# OpenDeck-r2_1_0.net
KiCad netlist of a schematic drawn in EAGLE
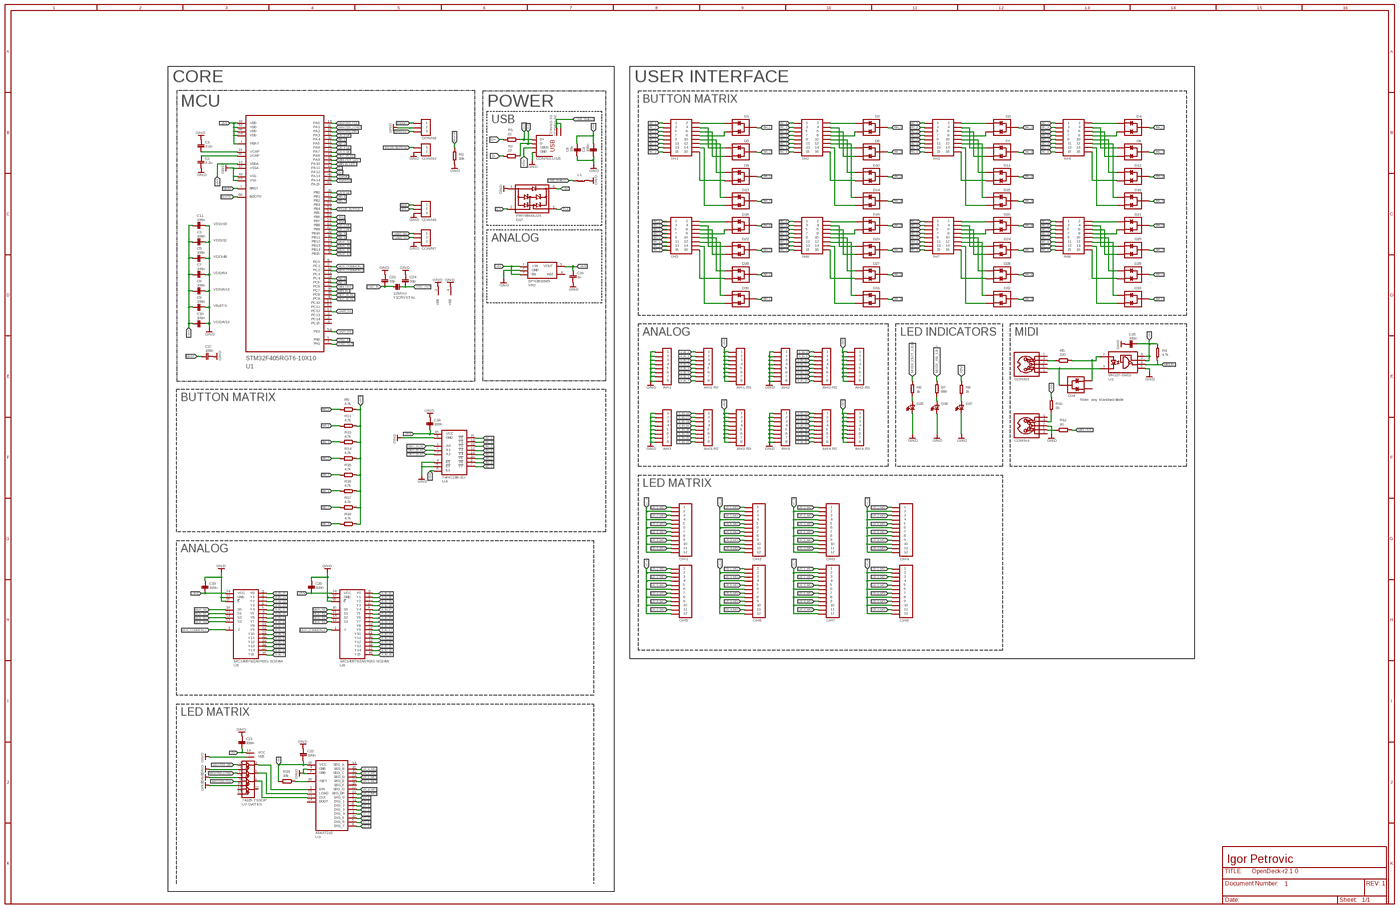
[diagram p0: schematic, sheet 1, overview]
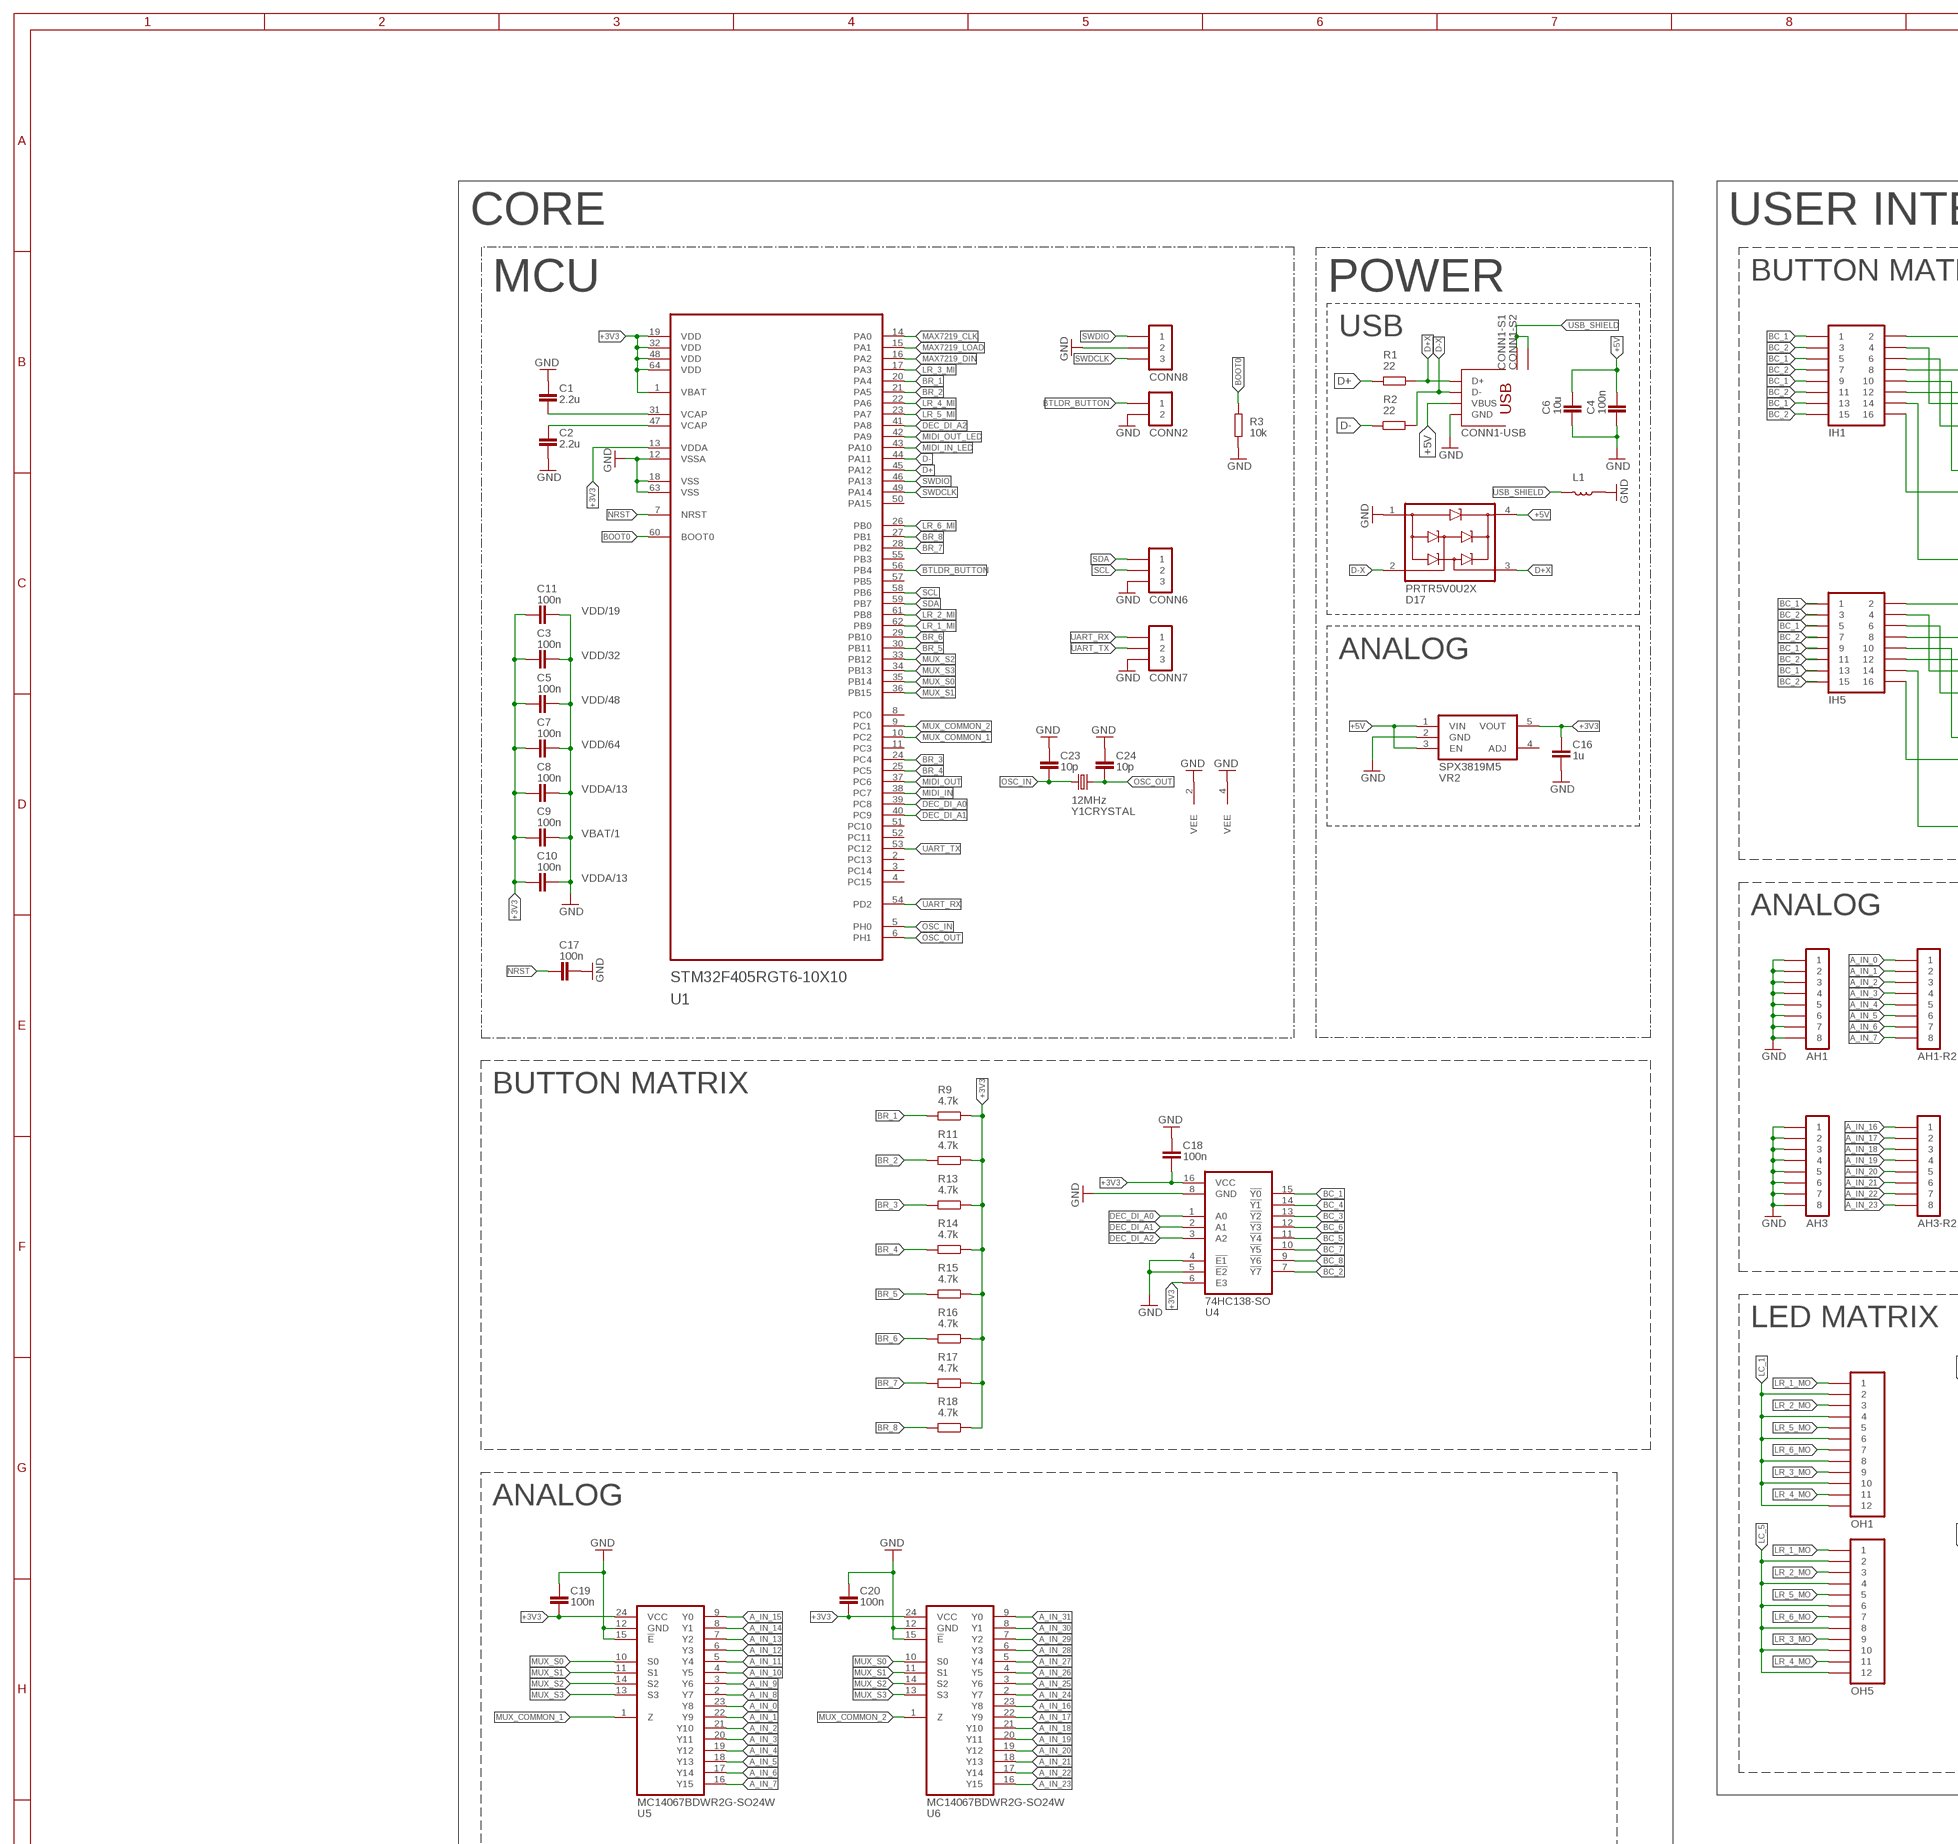
[diagram p1: schematic, sheet 1, part 1 of 4]
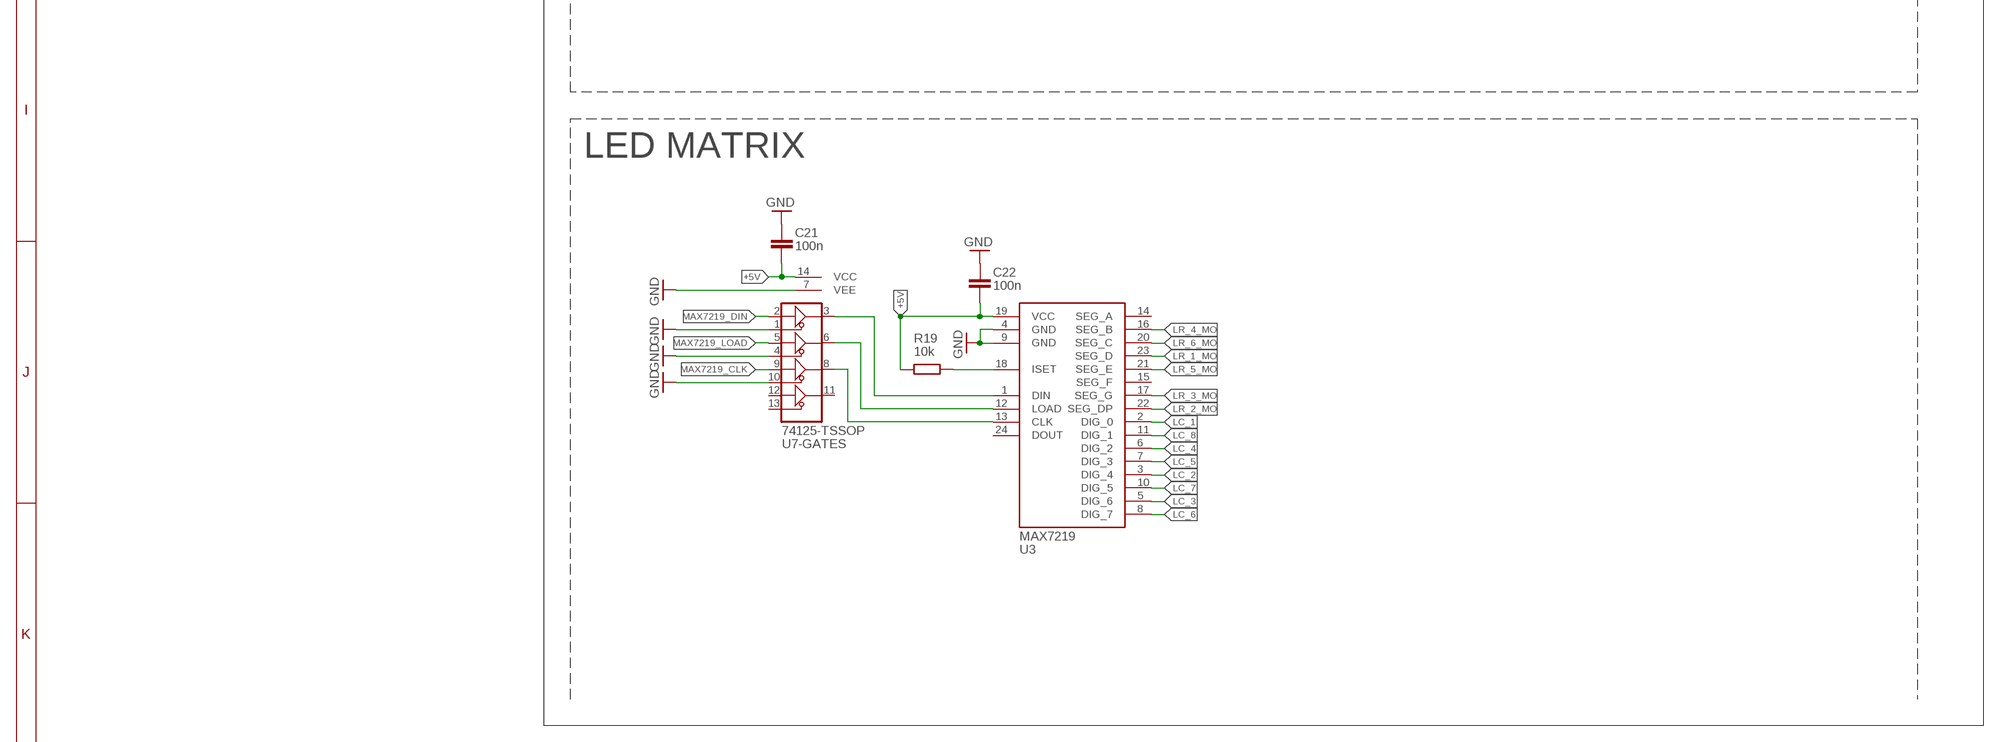
[diagram p2: schematic, sheet 1, part 2 of 4]
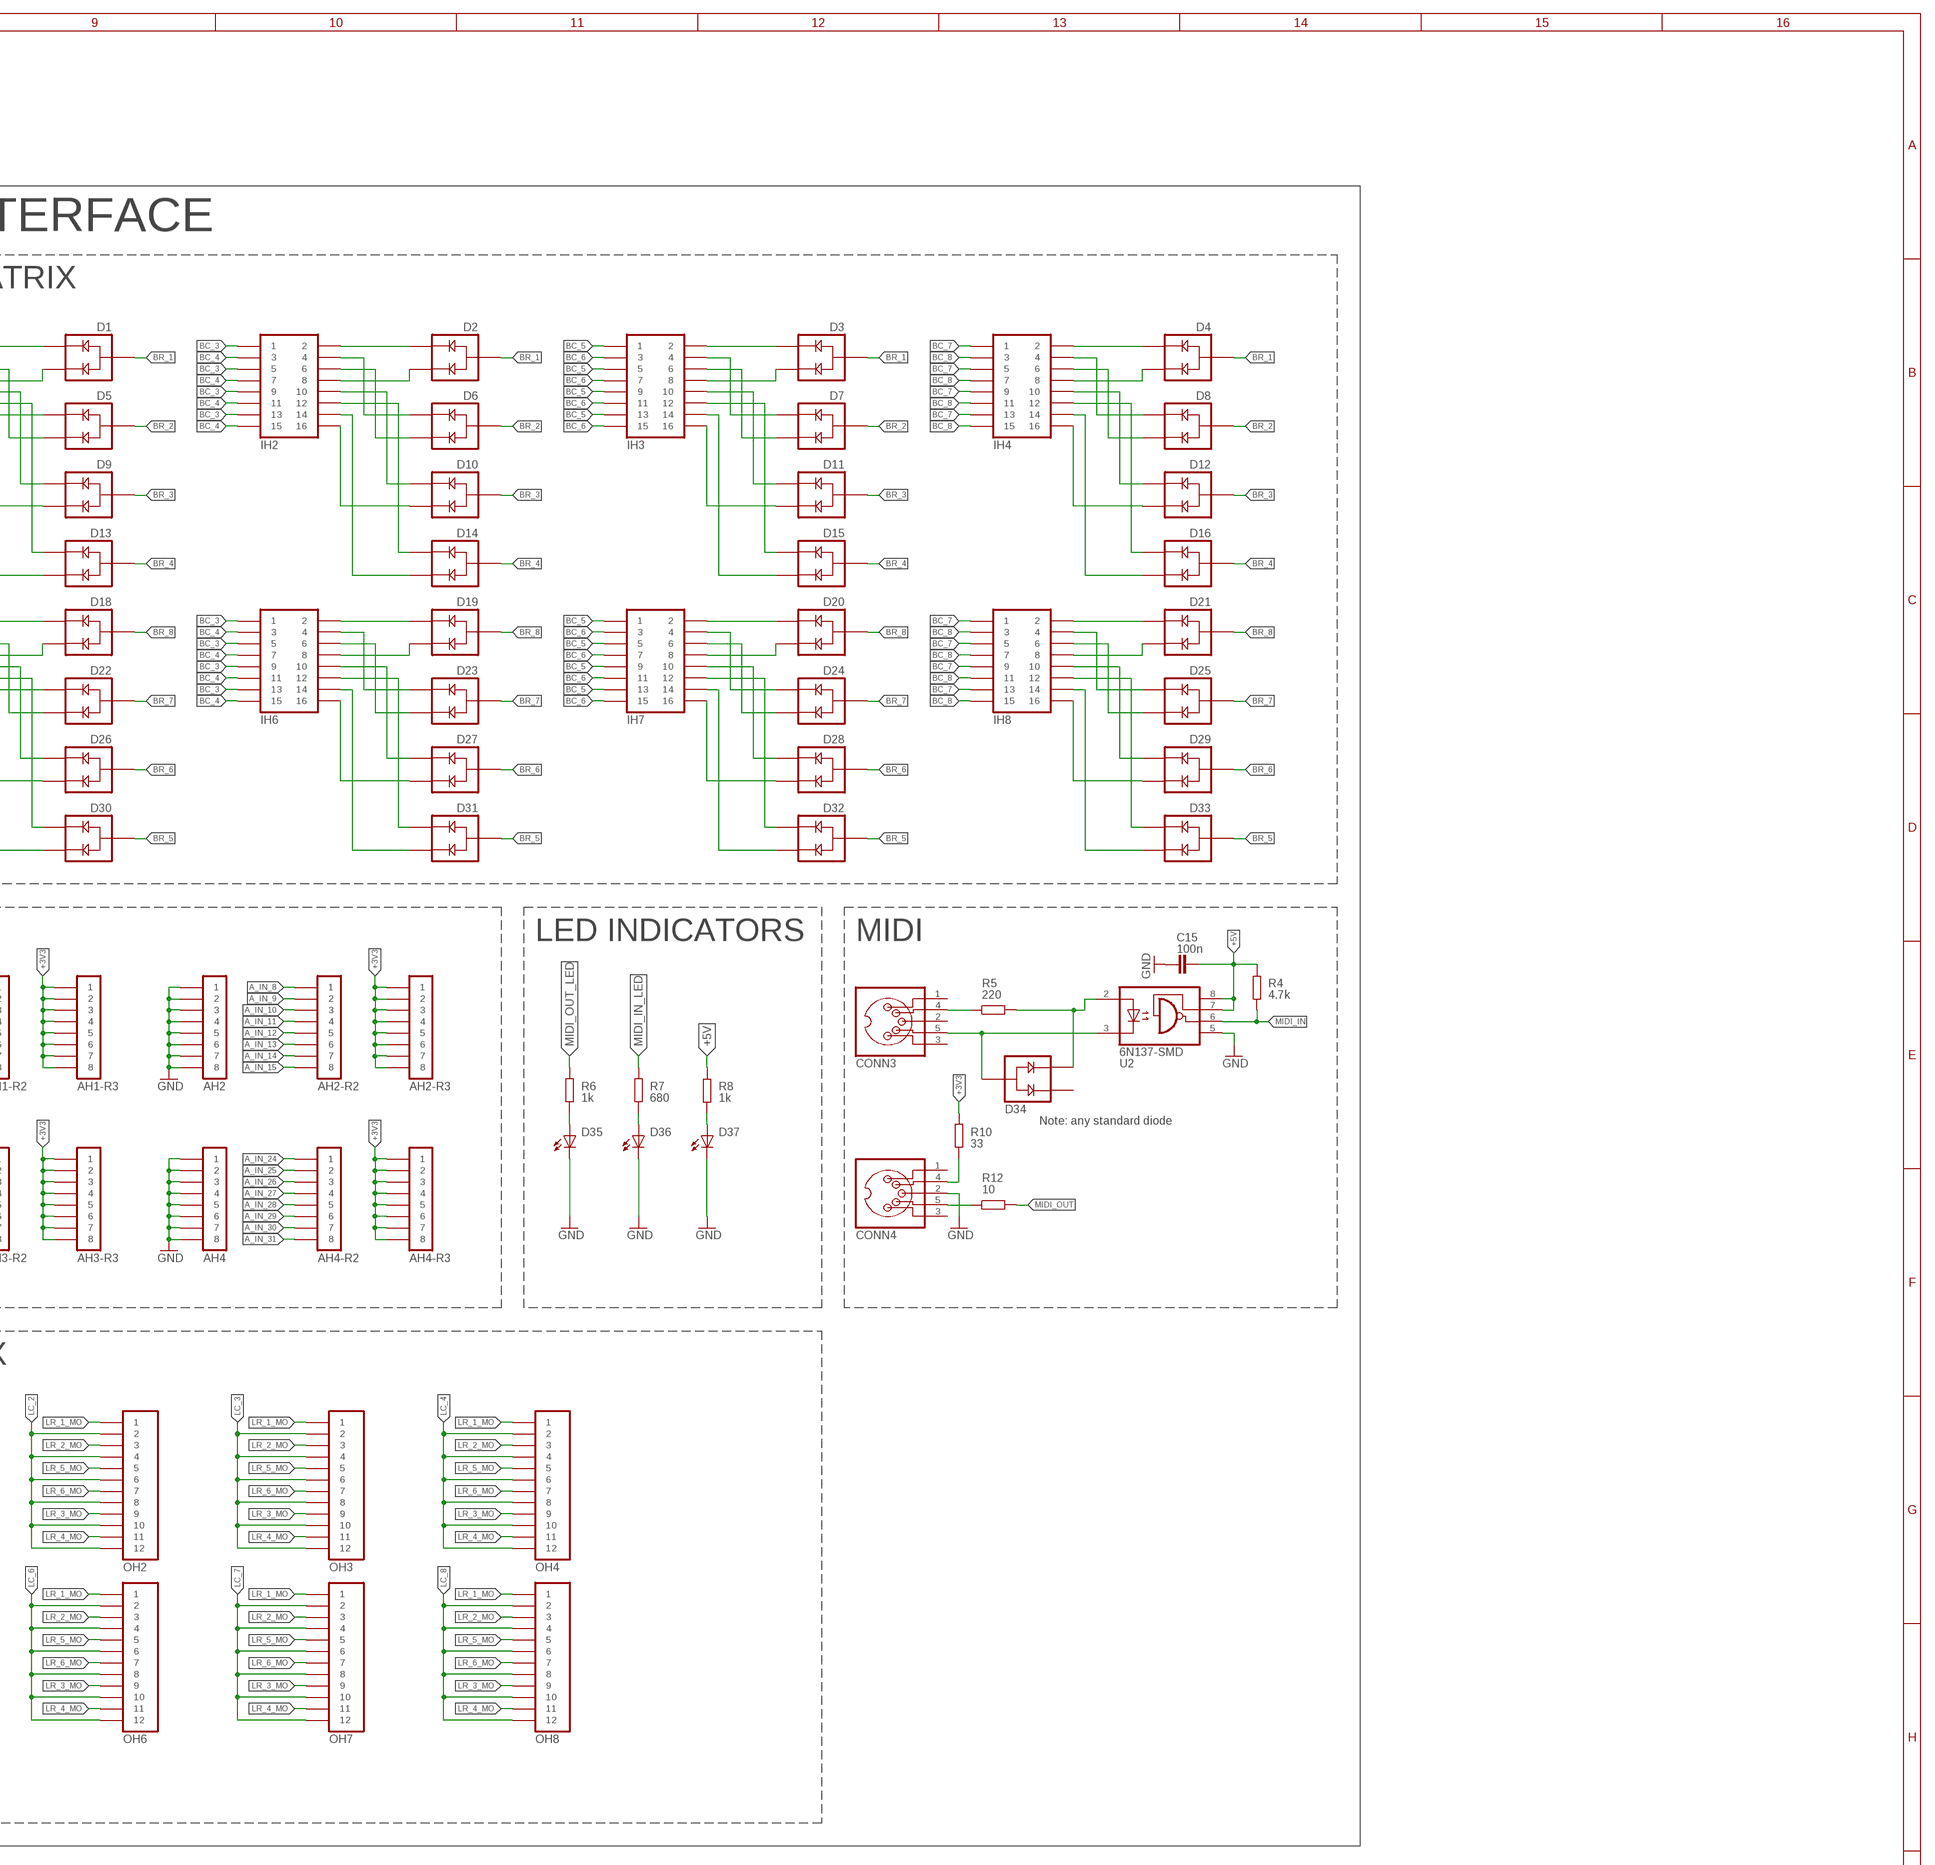
[diagram p3: schematic, sheet 1, part 3 of 4]
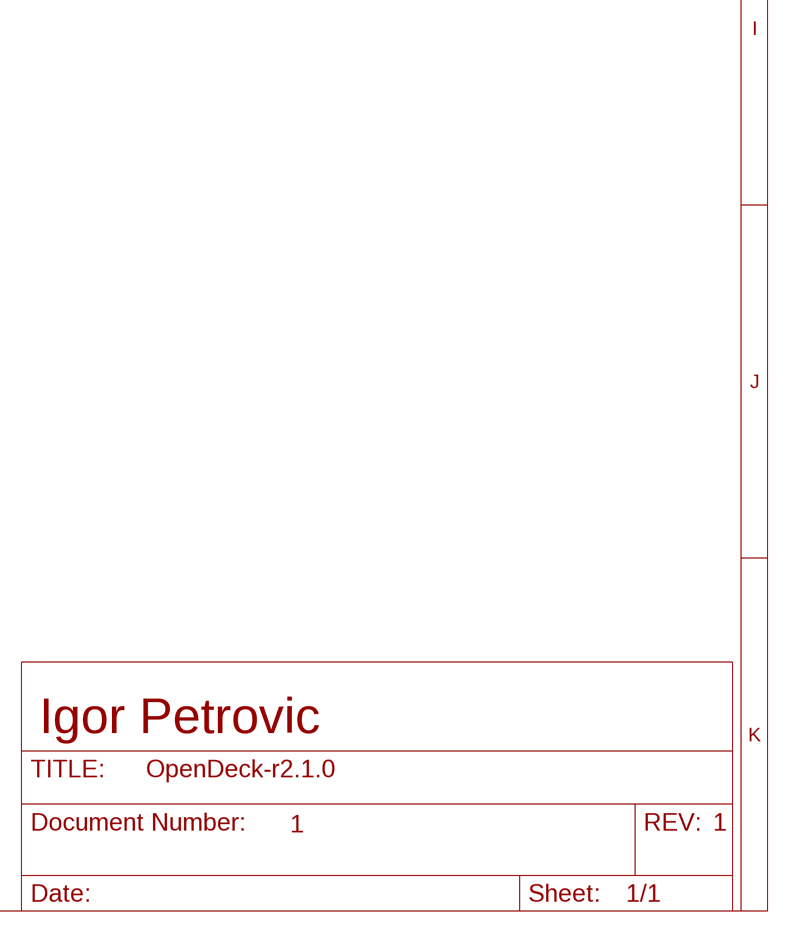
[diagram p4: schematic, sheet 1, part 4 of 4]

(export (version "E")
  (design (tool "Eeschema 10.0.6"))
  (components
    (comp (ref "AH1")
      (value "PINHD-3X08")
      (footprint "eagle-import:3X08-2.54")
      (libsource (lib "eagle-import") (part "PINHD-3X08"))
    )
    (comp (ref "AH2")
      (value "PINHD-3X08")
      (footprint "eagle-import:3X08-2.54")
      (libsource (lib "eagle-import") (part "PINHD-3X08"))
    )
    (comp (ref "AH3")
      (value "PINHD-3X08")
      (footprint "eagle-import:3X08-2.54")
      (libsource (lib "eagle-import") (part "PINHD-3X08"))
    )
    (comp (ref "AH4")
      (value "PINHD-3X08")
      (footprint "eagle-import:3X08-2.54")
      (libsource (lib "eagle-import") (part "PINHD-3X08"))
    )
    (comp (ref "C1")
      (value "2.2u")
      (footprint "eagle-import:C0402")
      (libsource (lib "eagle-import") (part "CAPACITOR-0402"))
    )
    (comp (ref "C2")
      (value "2.2u")
      (footprint "eagle-import:C0402")
      (libsource (lib "eagle-import") (part "CAPACITOR-0402"))
    )
    (comp (ref "C3")
      (value "100n")
      (footprint "eagle-import:C0402")
      (libsource (lib "eagle-import") (part "CAPACITOR-0402"))
    )
    (comp (ref "C4")
      (value "100n")
      (footprint "eagle-import:C0402")
      (libsource (lib "eagle-import") (part "CAPACITOR-0402"))
    )
    (comp (ref "C5")
      (value "100n")
      (footprint "eagle-import:C0402")
      (libsource (lib "eagle-import") (part "CAPACITOR-0402"))
    )
    (comp (ref "C6")
      (value "10u")
      (footprint "eagle-import:C0402")
      (libsource (lib "eagle-import") (part "CAPACITOR-0402"))
    )
    (comp (ref "C7")
      (value "100n")
      (footprint "eagle-import:C0402")
      (libsource (lib "eagle-import") (part "CAPACITOR-0402"))
    )
    (comp (ref "C8")
      (value "100n")
      (footprint "eagle-import:C0402")
      (libsource (lib "eagle-import") (part "CAPACITOR-0402"))
    )
    (comp (ref "C9")
      (value "100n")
      (footprint "eagle-import:C0402")
      (libsource (lib "eagle-import") (part "CAPACITOR-0402"))
    )
    (comp (ref "C10")
      (value "100n")
      (footprint "eagle-import:C0402")
      (libsource (lib "eagle-import") (part "CAPACITOR-0402"))
    )
    (comp (ref "C11")
      (value "100n")
      (footprint "eagle-import:C0402")
      (libsource (lib "eagle-import") (part "CAPACITOR-0402"))
    )
    (comp (ref "C15")
      (value "100n")
      (footprint "eagle-import:C0402")
      (libsource (lib "eagle-import") (part "CAPACITOR-0402"))
    )
    (comp (ref "C16")
      (value "1u")
      (footprint "eagle-import:C0402")
      (libsource (lib "eagle-import") (part "CAPACITOR-0402"))
    )
    (comp (ref "C17")
      (value "100n")
      (footprint "eagle-import:C0402")
      (libsource (lib "eagle-import") (part "CAPACITOR-0402"))
    )
    (comp (ref "C18")
      (value "100n")
      (footprint "eagle-import:C0402")
      (libsource (lib "eagle-import") (part "CAPACITOR-0402"))
    )
    (comp (ref "C19")
      (value "100n")
      (footprint "eagle-import:C0402")
      (libsource (lib "eagle-import") (part "CAPACITOR-0402"))
    )
    (comp (ref "C20")
      (value "100n")
      (footprint "eagle-import:C0402")
      (libsource (lib "eagle-import") (part "CAPACITOR-0402"))
    )
    (comp (ref "C21")
      (value "100n")
      (footprint "eagle-import:C0402")
      (libsource (lib "eagle-import") (part "CAPACITOR-0402"))
    )
    (comp (ref "C22")
      (value "100n")
      (footprint "eagle-import:C0402")
      (libsource (lib "eagle-import") (part "CAPACITOR-0402"))
    )
    (comp (ref "C23")
      (value "10p")
      (footprint "eagle-import:C0402")
      (libsource (lib "eagle-import") (part "CAPACITOR-0402"))
    )
    (comp (ref "C24")
      (value "10p")
      (footprint "eagle-import:C0402")
      (libsource (lib "eagle-import") (part "CAPACITOR-0402"))
    )
    (comp (ref "CONN1")
      (value "USB-B-H")
      (footprint "eagle-import:USB-B-PTH")
      (fields (field (name "LCSC") "C114097"))
      (libsource (lib "eagle-import") (part "USB-B-H"))
    )
    (comp (ref "CONN2")
      (value "PINHD-1X02-TH-2.54MM")
      (footprint "eagle-import:1X02-2.54-V")
      (libsource (lib "eagle-import") (part "PINHD-1X02-TH-2.54MM"))
    )
    (comp (ref "CONN3")
      (value "MIDI_CONN-STD")
      (footprint "eagle-import:DIN5")
      (fields (field (name "MANUFACTURER") "Switchcraft") (field (name "MPN") "57PC5F"))
      (libsource (lib "eagle-import") (part "MIDI_CONN-STD"))
    )
    (comp (ref "CONN4")
      (value "MIDI_CONN-STD")
      (footprint "eagle-import:DIN5")
      (fields (field (name "MANUFACTURER") "Switchcraft") (field (name "MPN") "57PC5F"))
      (libsource (lib "eagle-import") (part "MIDI_CONN-STD"))
    )
    (comp (ref "CONN6")
      (value "PINHD-1X03-TH-2.54MM")
      (footprint "eagle-import:1X03-2.54-V")
      (libsource (lib "eagle-import") (part "PINHD-1X03-TH-2.54MM"))
    )
    (comp (ref "CONN7")
      (value "PINHD-1X03-TH-2.54MM")
      (footprint "eagle-import:1X03-2.54-V")
      (libsource (lib "eagle-import") (part "PINHD-1X03-TH-2.54MM"))
    )
    (comp (ref "CONN8")
      (value "PINHD-1X03-TH-2.54MM")
      (footprint "eagle-import:1X03-2.54-V")
      (libsource (lib "eagle-import") (part "PINHD-1X03-TH-2.54MM"))
    )
    (comp (ref "D1")
      (value "BAW56")
      (footprint "eagle-import:SOT23")
      (fields (field (name "MANUFACTURER") "Multicomp") (field (name "MPN") "BAW56-7-F"))
      (libsource (lib "eagle-import") (part "BAW56"))
    )
    (comp (ref "D2")
      (value "BAW56")
      (footprint "eagle-import:SOT23")
      (fields (field (name "MANUFACTURER") "Multicomp") (field (name "MPN") "BAW56-7-F"))
      (libsource (lib "eagle-import") (part "BAW56"))
    )
    (comp (ref "D3")
      (value "BAW56")
      (footprint "eagle-import:SOT23")
      (fields (field (name "MANUFACTURER") "Multicomp") (field (name "MPN") "BAW56-7-F"))
      (libsource (lib "eagle-import") (part "BAW56"))
    )
    (comp (ref "D4")
      (value "BAW56")
      (footprint "eagle-import:SOT23")
      (fields (field (name "MANUFACTURER") "Multicomp") (field (name "MPN") "BAW56-7-F"))
      (libsource (lib "eagle-import") (part "BAW56"))
    )
    (comp (ref "D5")
      (value "BAW56")
      (footprint "eagle-import:SOT23")
      (fields (field (name "MANUFACTURER") "Multicomp") (field (name "MPN") "BAW56-7-F"))
      (libsource (lib "eagle-import") (part "BAW56"))
    )
    (comp (ref "D6")
      (value "BAW56")
      (footprint "eagle-import:SOT23")
      (fields (field (name "MANUFACTURER") "Multicomp") (field (name "MPN") "BAW56-7-F"))
      (libsource (lib "eagle-import") (part "BAW56"))
    )
    (comp (ref "D7")
      (value "BAW56")
      (footprint "eagle-import:SOT23")
      (fields (field (name "MANUFACTURER") "Multicomp") (field (name "MPN") "BAW56-7-F"))
      (libsource (lib "eagle-import") (part "BAW56"))
    )
    (comp (ref "D8")
      (value "BAW56")
      (footprint "eagle-import:SOT23")
      (fields (field (name "MANUFACTURER") "Multicomp") (field (name "MPN") "BAW56-7-F"))
      (libsource (lib "eagle-import") (part "BAW56"))
    )
    (comp (ref "D9")
      (value "BAW56")
      (footprint "eagle-import:SOT23")
      (fields (field (name "MANUFACTURER") "Multicomp") (field (name "MPN") "BAW56-7-F"))
      (libsource (lib "eagle-import") (part "BAW56"))
    )
    (comp (ref "D10")
      (value "BAW56")
      (footprint "eagle-import:SOT23")
      (fields (field (name "MANUFACTURER") "Multicomp") (field (name "MPN") "BAW56-7-F"))
      (libsource (lib "eagle-import") (part "BAW56"))
    )
    (comp (ref "D11")
      (value "BAW56")
      (footprint "eagle-import:SOT23")
      (fields (field (name "MANUFACTURER") "Multicomp") (field (name "MPN") "BAW56-7-F"))
      (libsource (lib "eagle-import") (part "BAW56"))
    )
    (comp (ref "D12")
      (value "BAW56")
      (footprint "eagle-import:SOT23")
      (fields (field (name "MANUFACTURER") "Multicomp") (field (name "MPN") "BAW56-7-F"))
      (libsource (lib "eagle-import") (part "BAW56"))
    )
    (comp (ref "D13")
      (value "BAW56")
      (footprint "eagle-import:SOT23")
      (fields (field (name "MANUFACTURER") "Multicomp") (field (name "MPN") "BAW56-7-F"))
      (libsource (lib "eagle-import") (part "BAW56"))
    )
    (comp (ref "D14")
      (value "BAW56")
      (footprint "eagle-import:SOT23")
      (fields (field (name "MANUFACTURER") "Multicomp") (field (name "MPN") "BAW56-7-F"))
      (libsource (lib "eagle-import") (part "BAW56"))
    )
    (comp (ref "D15")
      (value "BAW56")
      (footprint "eagle-import:SOT23")
      (fields (field (name "MANUFACTURER") "Multicomp") (field (name "MPN") "BAW56-7-F"))
      (libsource (lib "eagle-import") (part "BAW56"))
    )
    (comp (ref "D16")
      (value "BAW56")
      (footprint "eagle-import:SOT23")
      (fields (field (name "MANUFACTURER") "Multicomp") (field (name "MPN") "BAW56-7-F"))
      (libsource (lib "eagle-import") (part "BAW56"))
    )
    (comp (ref "D17")
      (value "PRTR5V0U2X")
      (footprint "eagle-import:SOT143")
      (fields (field (name "MANUFACTURER") "Nexperia"))
      (libsource (lib "eagle-import") (part "PRTR5V0U2X"))
    )
    (comp (ref "D18")
      (value "BAW56")
      (footprint "eagle-import:SOT23")
      (fields (field (name "MANUFACTURER") "Multicomp") (field (name "MPN") "BAW56-7-F"))
      (libsource (lib "eagle-import") (part "BAW56"))
    )
    (comp (ref "D19")
      (value "BAW56")
      (footprint "eagle-import:SOT23")
      (fields (field (name "MANUFACTURER") "Multicomp") (field (name "MPN") "BAW56-7-F"))
      (libsource (lib "eagle-import") (part "BAW56"))
    )
    (comp (ref "D20")
      (value "BAW56")
      (footprint "eagle-import:SOT23")
      (fields (field (name "MANUFACTURER") "Multicomp") (field (name "MPN") "BAW56-7-F"))
      (libsource (lib "eagle-import") (part "BAW56"))
    )
    (comp (ref "D21")
      (value "BAW56")
      (footprint "eagle-import:SOT23")
      (fields (field (name "MANUFACTURER") "Multicomp") (field (name "MPN") "BAW56-7-F"))
      (libsource (lib "eagle-import") (part "BAW56"))
    )
    (comp (ref "D22")
      (value "BAW56")
      (footprint "eagle-import:SOT23")
      (fields (field (name "MANUFACTURER") "Multicomp") (field (name "MPN") "BAW56-7-F"))
      (libsource (lib "eagle-import") (part "BAW56"))
    )
    (comp (ref "D23")
      (value "BAW56")
      (footprint "eagle-import:SOT23")
      (fields (field (name "MANUFACTURER") "Multicomp") (field (name "MPN") "BAW56-7-F"))
      (libsource (lib "eagle-import") (part "BAW56"))
    )
    (comp (ref "D24")
      (value "BAW56")
      (footprint "eagle-import:SOT23")
      (fields (field (name "MANUFACTURER") "Multicomp") (field (name "MPN") "BAW56-7-F"))
      (libsource (lib "eagle-import") (part "BAW56"))
    )
    (comp (ref "D25")
      (value "BAW56")
      (footprint "eagle-import:SOT23")
      (fields (field (name "MANUFACTURER") "Multicomp") (field (name "MPN") "BAW56-7-F"))
      (libsource (lib "eagle-import") (part "BAW56"))
    )
    (comp (ref "D26")
      (value "BAW56")
      (footprint "eagle-import:SOT23")
      (fields (field (name "MANUFACTURER") "Multicomp") (field (name "MPN") "BAW56-7-F"))
      (libsource (lib "eagle-import") (part "BAW56"))
    )
    (comp (ref "D27")
      (value "BAW56")
      (footprint "eagle-import:SOT23")
      (fields (field (name "MANUFACTURER") "Multicomp") (field (name "MPN") "BAW56-7-F"))
      (libsource (lib "eagle-import") (part "BAW56"))
    )
    (comp (ref "D28")
      (value "BAW56")
      (footprint "eagle-import:SOT23")
      (fields (field (name "MANUFACTURER") "Multicomp") (field (name "MPN") "BAW56-7-F"))
      (libsource (lib "eagle-import") (part "BAW56"))
    )
    (comp (ref "D29")
      (value "BAW56")
      (footprint "eagle-import:SOT23")
      (fields (field (name "MANUFACTURER") "Multicomp") (field (name "MPN") "BAW56-7-F"))
      (libsource (lib "eagle-import") (part "BAW56"))
    )
    (comp (ref "D30")
      (value "BAW56")
      (footprint "eagle-import:SOT23")
      (fields (field (name "MANUFACTURER") "Multicomp") (field (name "MPN") "BAW56-7-F"))
      (libsource (lib "eagle-import") (part "BAW56"))
    )
    (comp (ref "D31")
      (value "BAW56")
      (footprint "eagle-import:SOT23")
      (fields (field (name "MANUFACTURER") "Multicomp") (field (name "MPN") "BAW56-7-F"))
      (libsource (lib "eagle-import") (part "BAW56"))
    )
    (comp (ref "D32")
      (value "BAW56")
      (footprint "eagle-import:SOT23")
      (fields (field (name "MANUFACTURER") "Multicomp") (field (name "MPN") "BAW56-7-F"))
      (libsource (lib "eagle-import") (part "BAW56"))
    )
    (comp (ref "D33")
      (value "BAW56")
      (footprint "eagle-import:SOT23")
      (fields (field (name "MANUFACTURER") "Multicomp") (field (name "MPN") "BAW56-7-F"))
      (libsource (lib "eagle-import") (part "BAW56"))
    )
    (comp (ref "D34")
      (value "BAW56")
      (footprint "eagle-import:SOT23")
      (fields (field (name "MANUFACTURER") "Multicomp") (field (name "MPN") "BAW56-7-F"))
      (libsource (lib "eagle-import") (part "BAW56"))
    )
    (comp (ref "D35")
      (value "Red")
      (footprint "eagle-import:0805_LED")
      (libsource (lib "eagle-import") (part "LED-0805"))
    )
    (comp (ref "D36")
      (value "Yellow")
      (footprint "eagle-import:0805_LED")
      (libsource (lib "eagle-import") (part "LED-0805"))
    )
    (comp (ref "D37")
      (value "Green")
      (footprint "eagle-import:0805_LED")
      (libsource (lib "eagle-import") (part "LED-0805"))
    )
    (comp (ref "IH1")
      (value "PINHD-2X08-TH-2.54MM")
      (footprint "eagle-import:2X08-2.54")
      (libsource (lib "eagle-import") (part "PINHD-2X08-TH-2.54MM"))
    )
    (comp (ref "IH2")
      (value "PINHD-2X08-TH-2.54MM")
      (footprint "eagle-import:2X08-2.54")
      (libsource (lib "eagle-import") (part "PINHD-2X08-TH-2.54MM"))
    )
    (comp (ref "IH3")
      (value "PINHD-2X08-TH-2.54MM")
      (footprint "eagle-import:2X08-2.54")
      (libsource (lib "eagle-import") (part "PINHD-2X08-TH-2.54MM"))
    )
    (comp (ref "IH4")
      (value "PINHD-2X08-TH-2.54MM")
      (footprint "eagle-import:2X08-2.54")
      (libsource (lib "eagle-import") (part "PINHD-2X08-TH-2.54MM"))
    )
    (comp (ref "IH5")
      (value "PINHD-2X08-TH-2.54MM")
      (footprint "eagle-import:2X08-2.54")
      (libsource (lib "eagle-import") (part "PINHD-2X08-TH-2.54MM"))
    )
    (comp (ref "IH6")
      (value "PINHD-2X08-TH-2.54MM")
      (footprint "eagle-import:2X08-2.54")
      (libsource (lib "eagle-import") (part "PINHD-2X08-TH-2.54MM"))
    )
    (comp (ref "IH7")
      (value "PINHD-2X08-TH-2.54MM")
      (footprint "eagle-import:2X08-2.54")
      (libsource (lib "eagle-import") (part "PINHD-2X08-TH-2.54MM"))
    )
    (comp (ref "IH8")
      (value "PINHD-2X08-TH-2.54MM")
      (footprint "eagle-import:2X08-2.54")
      (libsource (lib "eagle-import") (part "PINHD-2X08-TH-2.54MM"))
    )
    (comp (ref "L1")
      (value "FERRITE_BEAD-BLM21PG221SN1D")
      (footprint "eagle-import:L0805")
      (fields (field (name "MANUFACTURER") "Murata") (field (name "MPN") "BLM21PG221SN1D"))
      (libsource (lib "eagle-import") (part "FERRITE_BEAD-BLM21PG221SN1D"))
    )
    (comp (ref "OH1")
      (value "PINHD-2X06-TH-2.54MM")
      (footprint "eagle-import:2X06-2.54-V")
      (libsource (lib "eagle-import") (part "PINHD-2X06-TH-2.54MM"))
    )
    (comp (ref "OH2")
      (value "PINHD-2X06-TH-2.54MM")
      (footprint "eagle-import:2X06-2.54-V")
      (libsource (lib "eagle-import") (part "PINHD-2X06-TH-2.54MM"))
    )
    (comp (ref "OH3")
      (value "PINHD-2X06-TH-2.54MM")
      (footprint "eagle-import:2X06-2.54-V")
      (libsource (lib "eagle-import") (part "PINHD-2X06-TH-2.54MM"))
    )
    (comp (ref "OH4")
      (value "PINHD-2X06-TH-2.54MM")
      (footprint "eagle-import:2X06-2.54-V")
      (libsource (lib "eagle-import") (part "PINHD-2X06-TH-2.54MM"))
    )
    (comp (ref "OH5")
      (value "PINHD-2X06-TH-2.54MM")
      (footprint "eagle-import:2X06-2.54-V")
      (libsource (lib "eagle-import") (part "PINHD-2X06-TH-2.54MM"))
    )
    (comp (ref "OH6")
      (value "PINHD-2X06-TH-2.54MM")
      (footprint "eagle-import:2X06-2.54-V")
      (libsource (lib "eagle-import") (part "PINHD-2X06-TH-2.54MM"))
    )
    (comp (ref "OH7")
      (value "PINHD-2X06-TH-2.54MM")
      (footprint "eagle-import:2X06-2.54-V")
      (libsource (lib "eagle-import") (part "PINHD-2X06-TH-2.54MM"))
    )
    (comp (ref "OH8")
      (value "PINHD-2X06-TH-2.54MM")
      (footprint "eagle-import:2X06-2.54-V")
      (libsource (lib "eagle-import") (part "PINHD-2X06-TH-2.54MM"))
    )
    (comp (ref "R1")
      (value "22")
      (footprint "eagle-import:R0402")
      (libsource (lib "eagle-import") (part "RESISTOR-0402"))
    )
    (comp (ref "R2")
      (value "22")
      (footprint "eagle-import:R0402")
      (libsource (lib "eagle-import") (part "RESISTOR-0402"))
    )
    (comp (ref "R3")
      (value "10k")
      (footprint "eagle-import:R0402")
      (libsource (lib "eagle-import") (part "RESISTOR-0402"))
    )
    (comp (ref "R4")
      (value "4.7k")
      (footprint "eagle-import:R0402")
      (libsource (lib "eagle-import") (part "RESISTOR-0402"))
    )
    (comp (ref "R5")
      (value "220")
      (footprint "eagle-import:R0402")
      (libsource (lib "eagle-import") (part "RESISTOR-0402"))
    )
    (comp (ref "R6")
      (value "1k")
      (footprint "eagle-import:R0402")
      (libsource (lib "eagle-import") (part "RESISTOR-0402"))
    )
    (comp (ref "R7")
      (value "680")
      (footprint "eagle-import:R0402")
      (libsource (lib "eagle-import") (part "RESISTOR-0402"))
    )
    (comp (ref "R8")
      (value "1k")
      (footprint "eagle-import:R0402")
      (libsource (lib "eagle-import") (part "RESISTOR-0402"))
    )
    (comp (ref "R9")
      (value "4.7k")
      (footprint "eagle-import:R0402")
      (libsource (lib "eagle-import") (part "RESISTOR-0402"))
    )
    (comp (ref "R10")
      (value "33")
      (footprint "eagle-import:R0402")
      (libsource (lib "eagle-import") (part "RESISTOR-0402"))
    )
    (comp (ref "R11")
      (value "4.7k")
      (footprint "eagle-import:R0402")
      (libsource (lib "eagle-import") (part "RESISTOR-0402"))
    )
    (comp (ref "R12")
      (value "10")
      (footprint "eagle-import:R0402")
      (libsource (lib "eagle-import") (part "RESISTOR-0402"))
    )
    (comp (ref "R13")
      (value "4.7k")
      (footprint "eagle-import:R0402")
      (libsource (lib "eagle-import") (part "RESISTOR-0402"))
    )
    (comp (ref "R14")
      (value "4.7k")
      (footprint "eagle-import:R0402")
      (libsource (lib "eagle-import") (part "RESISTOR-0402"))
    )
    (comp (ref "R15")
      (value "4.7k")
      (footprint "eagle-import:R0402")
      (libsource (lib "eagle-import") (part "RESISTOR-0402"))
    )
    (comp (ref "R16")
      (value "4.7k")
      (footprint "eagle-import:R0402")
      (libsource (lib "eagle-import") (part "RESISTOR-0402"))
    )
    (comp (ref "R17")
      (value "4.7k")
      (footprint "eagle-import:R0402")
      (libsource (lib "eagle-import") (part "RESISTOR-0402"))
    )
    (comp (ref "R18")
      (value "4.7k")
      (footprint "eagle-import:R0402")
      (libsource (lib "eagle-import") (part "RESISTOR-0402"))
    )
    (comp (ref "R19")
      (value "10k")
      (footprint "eagle-import:R0402")
      (libsource (lib "eagle-import") (part "RESISTOR-0402"))
    )
    (comp (ref "U1")
      (value "STM32F405RGT6-10X10")
      (footprint "eagle-import:TQFP-64-10X10")
      (fields (field (name "MANUFACTURER") "ST Microelectronics") (field (name "MPN") "STM32F405RGT6"))
      (libsource (lib "eagle-import") (part "STM32F405RGT6-10X10"))
    )
    (comp (ref "U2")
      (value "6N137-SMD")
      (footprint "eagle-import:SMD-8")
      (fields (field (name "MANUFACTURER") "Lite-On") (field (name "MPN") "6N137S"))
      (libsource (lib "eagle-import") (part "6N137-SMD"))
    )
    (comp (ref "U3")
      (value "MAX7219")
      (footprint "eagle-import:SO24-W")
      (libsource (lib "eagle-import") (part "MAX7219"))
    )
    (comp (ref "U4")
      (value "74HC138-SO")
      (footprint "eagle-import:SO16")
      (fields (field (name "MANUFACTURER") "Nexperia") (field (name "MPN") "74HC138D"))
      (libsource (lib "eagle-import") (part "74138-SOHC"))
    )
    (comp (ref "U5")
      (value "MC14067BDWR2G-SO24W")
      (footprint "eagle-import:SO24-W")
      (fields (field (name "MANUFACTURER") "ON Semiconductor") (field (name "MPN") "MC14067BDWR2G"))
      (libsource (lib "eagle-import") (part "MC14067BDWR2G-SO24W"))
    )
    (comp (ref "U6")
      (value "MC14067BDWR2G-SO24W")
      (footprint "eagle-import:SO24-W")
      (fields (field (name "MANUFACTURER") "ON Semiconductor") (field (name "MPN") "MC14067BDWR2G"))
      (libsource (lib "eagle-import") (part "MC14067BDWR2G-SO24W"))
    )
    (comp (ref "U7")
      (value "74125-TSSOP")
      (footprint "eagle-import:TSSOP14")
      (fields (field (name "LCSC") "C36365"))
      (libsource (lib "eagle-import") (part "74125-TSSOP"))
    )
    (comp (ref "VR2")
      (value "SPX3819M5")
      (footprint "eagle-import:SOT23-5")
      (libsource (lib "eagle-import") (part "SPX3819M5"))
    )
    (comp (ref "Y1")
      (value "12MHz")
      (footprint "eagle-import:CRYSTAL-SMD-2.5X2")
      (fields
        (field (name "MANUFACTURER") "ECS")
        (field (name "MPN") "ECS-160-10-36-CKM-TR")
        (field (name "LCSC") "C254284")
      )
      (libsource (lib "eagle-import") (part "CRYSTAL-4P-SMD-2.5X2"))
    )
  )
  (nets
    (net (code "1") (name "+3V3") (class "Default")
      (node (ref "AH1") (pin "12") (pinfunction "4_12") (pintype "passive"))
      (node (ref "AH1") (pin "15") (pinfunction "5_15") (pintype "passive"))
      (node (ref "AH1") (pin "18") (pinfunction "6_18") (pintype "passive"))
      (node (ref "AH1") (pin "21") (pinfunction "7_21") (pintype "passive"))
      (node (ref "AH1") (pin "24") (pinfunction "8_24") (pintype "passive"))
      (node (ref "AH1") (pin "3") (pinfunction "1_3") (pintype "passive"))
      (node (ref "AH1") (pin "6") (pinfunction "2_6") (pintype "passive"))
      (node (ref "AH1") (pin "9") (pinfunction "3_9") (pintype "passive"))
      (node (ref "AH2") (pin "12") (pinfunction "4_12") (pintype "passive"))
      (node (ref "AH2") (pin "15") (pinfunction "5_15") (pintype "passive"))
      (node (ref "AH2") (pin "18") (pinfunction "6_18") (pintype "passive"))
      (node (ref "AH2") (pin "21") (pinfunction "7_21") (pintype "passive"))
      (node (ref "AH2") (pin "24") (pinfunction "8_24") (pintype "passive"))
      (node (ref "AH2") (pin "3") (pinfunction "1_3") (pintype "passive"))
      (node (ref "AH2") (pin "6") (pinfunction "2_6") (pintype "passive"))
      (node (ref "AH2") (pin "9") (pinfunction "3_9") (pintype "passive"))
      (node (ref "AH3") (pin "12") (pinfunction "4_12") (pintype "passive"))
      (node (ref "AH3") (pin "15") (pinfunction "5_15") (pintype "passive"))
      (node (ref "AH3") (pin "18") (pinfunction "6_18") (pintype "passive"))
      (node (ref "AH3") (pin "21") (pinfunction "7_21") (pintype "passive"))
      (node (ref "AH3") (pin "24") (pinfunction "8_24") (pintype "passive"))
      (node (ref "AH3") (pin "3") (pinfunction "1_3") (pintype "passive"))
      (node (ref "AH3") (pin "6") (pinfunction "2_6") (pintype "passive"))
      (node (ref "AH3") (pin "9") (pinfunction "3_9") (pintype "passive"))
      (node (ref "AH4") (pin "12") (pinfunction "4_12") (pintype "passive"))
      (node (ref "AH4") (pin "15") (pinfunction "5_15") (pintype "passive"))
      (node (ref "AH4") (pin "18") (pinfunction "6_18") (pintype "passive"))
      (node (ref "AH4") (pin "21") (pinfunction "7_21") (pintype "passive"))
      (node (ref "AH4") (pin "24") (pinfunction "8_24") (pintype "passive"))
      (node (ref "AH4") (pin "3") (pinfunction "1_3") (pintype "passive"))
      (node (ref "AH4") (pin "6") (pinfunction "2_6") (pintype "passive"))
      (node (ref "AH4") (pin "9") (pinfunction "3_9") (pintype "passive"))
      (node (ref "C10") (pin "1") (pinfunction "1_1") (pintype "passive"))
      (node (ref "C11") (pin "1") (pinfunction "1_1") (pintype "passive"))
      (node (ref "C16") (pin "1") (pinfunction "1_1") (pintype "passive"))
      (node (ref "C18") (pin "2") (pinfunction "2_2") (pintype "passive"))
      (node (ref "C19") (pin "2") (pinfunction "2_2") (pintype "passive"))
      (node (ref "C20") (pin "2") (pinfunction "2_2") (pintype "passive"))
      (node (ref "C3") (pin "1") (pinfunction "1_1") (pintype "passive"))
      (node (ref "C5") (pin "1") (pinfunction "1_1") (pintype "passive"))
      (node (ref "C7") (pin "1") (pinfunction "1_1") (pintype "passive"))
      (node (ref "C8") (pin "1") (pinfunction "1_1") (pintype "passive"))
      (node (ref "C9") (pin "1") (pinfunction "1_1") (pintype "passive"))
      (node (ref "R10") (pin "2") (pinfunction "2_2") (pintype "passive"))
      (node (ref "R11") (pin "1") (pinfunction "1_1") (pintype "passive"))
      (node (ref "R13") (pin "1") (pinfunction "1_1") (pintype "passive"))
      (node (ref "R14") (pin "1") (pinfunction "1_1") (pintype "passive"))
      (node (ref "R15") (pin "1") (pinfunction "1_1") (pintype "passive"))
      (node (ref "R16") (pin "1") (pinfunction "1_1") (pintype "passive"))
      (node (ref "R17") (pin "1") (pinfunction "1_1") (pintype "passive"))
      (node (ref "R18") (pin "1") (pinfunction "1_1") (pintype "passive"))
      (node (ref "R9") (pin "1") (pinfunction "1_1") (pintype "passive"))
      (node (ref "U1") (pin "1") (pinfunction "VBAT_1") (pintype "bidirectional"))
      (node (ref "U1") (pin "13") (pinfunction "VDDA_13") (pintype "bidirectional"))
      (node (ref "U1") (pin "19") (pinfunction "VDD_19") (pintype "bidirectional"))
      (node (ref "U1") (pin "32") (pinfunction "VDD_32") (pintype "bidirectional"))
      (node (ref "U1") (pin "48") (pinfunction "VDD_48") (pintype "bidirectional"))
      (node (ref "U1") (pin "64") (pinfunction "VDD_64") (pintype "bidirectional"))
      (node (ref "U4") (pin "16") (pinfunction "VCC_16") (pintype "power_in"))
      (node (ref "U4") (pin "6") (pinfunction "E3_6") (pintype "input"))
      (node (ref "U5") (pin "24") (pinfunction "VCC_24") (pintype "passive"))
      (node (ref "U6") (pin "24") (pinfunction "VCC_24") (pintype "passive"))
      (node (ref "VR2") (pin "5") (pinfunction "VOUT_5") (pintype "passive"))
    )
    (net (code "2") (name "+5V") (class "Default")
      (node (ref "C15") (pin "2") (pinfunction "2_2") (pintype "passive"))
      (node (ref "C21") (pin "1") (pinfunction "1_1") (pintype "passive"))
      (node (ref "C22") (pin "1") (pinfunction "1_1") (pintype "passive"))
      (node (ref "C4") (pin "2") (pinfunction "2_2") (pintype "passive"))
      (node (ref "C6") (pin "2") (pinfunction "2_2") (pintype "passive"))
      (node (ref "CONN1") (pin "VBUS") (pinfunction "VBUS_VBUS") (pintype "bidirectional"))
      (node (ref "D17") (pin "4") (pinfunction "VCC_4") (pintype "passive"))
      (node (ref "R19") (pin "2") (pinfunction "2_2") (pintype "passive"))
      (node (ref "R4") (pin "1") (pinfunction "1_1") (pintype "passive"))
      (node (ref "R8") (pin "1") (pinfunction "1_1") (pintype "passive"))
      (node (ref "U2") (pin "7") (pinfunction "VE_7") (pintype "input"))
      (node (ref "U2") (pin "8") (pinfunction "VCC_8") (pintype "power_in"))
      (node (ref "U3") (pin "19") (pinfunction "VCC_19") (pintype "power_in"))
      (node (ref "U7") (pin "14") (pinfunction "VCC_14") (pintype "passive"))
      (node (ref "VR2") (pin "1") (pinfunction "VIN_1") (pintype "passive"))
      (node (ref "VR2") (pin "3") (pinfunction "EN_3") (pintype "passive"))
    )
    (net (code "3") (name "A_IN_0") (class "Default")
      (node (ref "AH1") (pin "2") (pinfunction "1_2") (pintype "passive"))
      (node (ref "U5") (pin "23") (pinfunction "Y8_23") (pintype "bidirectional"))
    )
    (net (code "4") (name "A_IN_1") (class "Default")
      (node (ref "AH1") (pin "5") (pinfunction "2_5") (pintype "passive"))
      (node (ref "U5") (pin "22") (pinfunction "Y9_22") (pintype "bidirectional"))
    )
    (net (code "5") (name "A_IN_2") (class "Default")
      (node (ref "AH1") (pin "8") (pinfunction "3_8") (pintype "passive"))
      (node (ref "U5") (pin "21") (pinfunction "Y10_21") (pintype "bidirectional"))
    )
    (net (code "6") (name "A_IN_3") (class "Default")
      (node (ref "AH1") (pin "11") (pinfunction "4_11") (pintype "passive"))
      (node (ref "U5") (pin "20") (pinfunction "Y11_20") (pintype "bidirectional"))
    )
    (net (code "7") (name "A_IN_4") (class "Default")
      (node (ref "AH1") (pin "14") (pinfunction "5_14") (pintype "passive"))
      (node (ref "U5") (pin "19") (pinfunction "Y12_19") (pintype "bidirectional"))
    )
    (net (code "8") (name "A_IN_5") (class "Default")
      (node (ref "AH1") (pin "17") (pinfunction "6_17") (pintype "passive"))
      (node (ref "U5") (pin "18") (pinfunction "Y13_18") (pintype "bidirectional"))
    )
    (net (code "9") (name "A_IN_6") (class "Default")
      (node (ref "AH1") (pin "20") (pinfunction "7_20") (pintype "passive"))
      (node (ref "U5") (pin "17") (pinfunction "Y14_17") (pintype "bidirectional"))
    )
    (net (code "10") (name "A_IN_7") (class "Default")
      (node (ref "AH1") (pin "23") (pinfunction "8_23") (pintype "passive"))
      (node (ref "U5") (pin "16") (pinfunction "Y15_16") (pintype "bidirectional"))
    )
    (net (code "11") (name "A_IN_8") (class "Default")
      (node (ref "AH2") (pin "2") (pinfunction "1_2") (pintype "passive"))
      (node (ref "U5") (pin "2") (pinfunction "Y7_2") (pintype "bidirectional"))
    )
    (net (code "12") (name "A_IN_9") (class "Default")
      (node (ref "AH2") (pin "5") (pinfunction "2_5") (pintype "passive"))
      (node (ref "U5") (pin "3") (pinfunction "Y6_3") (pintype "bidirectional"))
    )
    (net (code "13") (name "A_IN_10") (class "Default")
      (node (ref "AH2") (pin "8") (pinfunction "3_8") (pintype "passive"))
      (node (ref "U5") (pin "4") (pinfunction "Y5_4") (pintype "bidirectional"))
    )
    (net (code "14") (name "A_IN_11") (class "Default")
      (node (ref "AH2") (pin "11") (pinfunction "4_11") (pintype "passive"))
      (node (ref "U5") (pin "5") (pinfunction "Y4_5") (pintype "bidirectional"))
    )
    (net (code "15") (name "A_IN_12") (class "Default")
      (node (ref "AH2") (pin "14") (pinfunction "5_14") (pintype "passive"))
      (node (ref "U5") (pin "6") (pinfunction "Y3_6") (pintype "bidirectional"))
    )
    (net (code "16") (name "A_IN_13") (class "Default")
      (node (ref "AH2") (pin "17") (pinfunction "6_17") (pintype "passive"))
      (node (ref "U5") (pin "7") (pinfunction "Y2_7") (pintype "bidirectional"))
    )
    (net (code "17") (name "A_IN_14") (class "Default")
      (node (ref "AH2") (pin "20") (pinfunction "7_20") (pintype "passive"))
      (node (ref "U5") (pin "8") (pinfunction "Y1_8") (pintype "bidirectional"))
    )
    (net (code "18") (name "A_IN_15") (class "Default")
      (node (ref "AH2") (pin "23") (pinfunction "8_23") (pintype "passive"))
      (node (ref "U5") (pin "9") (pinfunction "Y0_9") (pintype "bidirectional"))
    )
    (net (code "19") (name "A_IN_16") (class "Default")
      (node (ref "AH3") (pin "2") (pinfunction "1_2") (pintype "passive"))
      (node (ref "U6") (pin "23") (pinfunction "Y8_23") (pintype "bidirectional"))
    )
    (net (code "20") (name "A_IN_17") (class "Default")
      (node (ref "AH3") (pin "5") (pinfunction "2_5") (pintype "passive"))
      (node (ref "U6") (pin "22") (pinfunction "Y9_22") (pintype "bidirectional"))
    )
    (net (code "21") (name "A_IN_18") (class "Default")
      (node (ref "AH3") (pin "8") (pinfunction "3_8") (pintype "passive"))
      (node (ref "U6") (pin "21") (pinfunction "Y10_21") (pintype "bidirectional"))
    )
    (net (code "22") (name "A_IN_19") (class "Default")
      (node (ref "AH3") (pin "11") (pinfunction "4_11") (pintype "passive"))
      (node (ref "U6") (pin "20") (pinfunction "Y11_20") (pintype "bidirectional"))
    )
    (net (code "23") (name "A_IN_20") (class "Default")
      (node (ref "AH3") (pin "14") (pinfunction "5_14") (pintype "passive"))
      (node (ref "U6") (pin "19") (pinfunction "Y12_19") (pintype "bidirectional"))
    )
    (net (code "24") (name "A_IN_21") (class "Default")
      (node (ref "AH3") (pin "17") (pinfunction "6_17") (pintype "passive"))
      (node (ref "U6") (pin "18") (pinfunction "Y13_18") (pintype "bidirectional"))
    )
    (net (code "25") (name "A_IN_22") (class "Default")
      (node (ref "AH3") (pin "20") (pinfunction "7_20") (pintype "passive"))
      (node (ref "U6") (pin "17") (pinfunction "Y14_17") (pintype "bidirectional"))
    )
    (net (code "26") (name "A_IN_23") (class "Default")
      (node (ref "AH3") (pin "23") (pinfunction "8_23") (pintype "passive"))
      (node (ref "U6") (pin "16") (pinfunction "Y15_16") (pintype "bidirectional"))
    )
    (net (code "27") (name "A_IN_24") (class "Default")
      (node (ref "AH4") (pin "2") (pinfunction "1_2") (pintype "passive"))
      (node (ref "U6") (pin "2") (pinfunction "Y7_2") (pintype "bidirectional"))
    )
    (net (code "28") (name "A_IN_25") (class "Default")
      (node (ref "AH4") (pin "5") (pinfunction "2_5") (pintype "passive"))
      (node (ref "U6") (pin "3") (pinfunction "Y6_3") (pintype "bidirectional"))
    )
    (net (code "29") (name "A_IN_26") (class "Default")
      (node (ref "AH4") (pin "8") (pinfunction "3_8") (pintype "passive"))
      (node (ref "U6") (pin "4") (pinfunction "Y5_4") (pintype "bidirectional"))
    )
    (net (code "30") (name "A_IN_27") (class "Default")
      (node (ref "AH4") (pin "11") (pinfunction "4_11") (pintype "passive"))
      (node (ref "U6") (pin "5") (pinfunction "Y4_5") (pintype "bidirectional"))
    )
    (net (code "31") (name "A_IN_28") (class "Default")
      (node (ref "AH4") (pin "14") (pinfunction "5_14") (pintype "passive"))
      (node (ref "U6") (pin "6") (pinfunction "Y3_6") (pintype "bidirectional"))
    )
    (net (code "32") (name "A_IN_29") (class "Default")
      (node (ref "AH4") (pin "17") (pinfunction "6_17") (pintype "passive"))
      (node (ref "U6") (pin "7") (pinfunction "Y2_7") (pintype "bidirectional"))
    )
    (net (code "33") (name "A_IN_30") (class "Default")
      (node (ref "AH4") (pin "20") (pinfunction "7_20") (pintype "passive"))
      (node (ref "U6") (pin "8") (pinfunction "Y1_8") (pintype "bidirectional"))
    )
    (net (code "34") (name "A_IN_31") (class "Default")
      (node (ref "AH4") (pin "23") (pinfunction "8_23") (pintype "passive"))
      (node (ref "U6") (pin "9") (pinfunction "Y0_9") (pintype "bidirectional"))
    )
    (net (code "35") (name "BC_1") (class "Default")
      (node (ref "IH1") (pin "1") (pinfunction "1_1") (pintype "passive"))
      (node (ref "IH1") (pin "13") (pinfunction "13_13") (pintype "passive"))
      (node (ref "IH1") (pin "5") (pinfunction "5_5") (pintype "passive"))
      (node (ref "IH1") (pin "9") (pinfunction "9_9") (pintype "passive"))
      (node (ref "IH5") (pin "1") (pinfunction "1_1") (pintype "passive"))
      (node (ref "IH5") (pin "13") (pinfunction "13_13") (pintype "passive"))
      (node (ref "IH5") (pin "5") (pinfunction "5_5") (pintype "passive"))
      (node (ref "IH5") (pin "9") (pinfunction "9_9") (pintype "passive"))
      (node (ref "U4") (pin "15") (pinfunction "~{Y0}_15") (pintype "output"))
    )
    (net (code "36") (name "BC_2") (class "Default")
      (node (ref "IH1") (pin "11") (pinfunction "11_11") (pintype "passive"))
      (node (ref "IH1") (pin "15") (pinfunction "15_15") (pintype "passive"))
      (node (ref "IH1") (pin "3") (pinfunction "3_3") (pintype "passive"))
      (node (ref "IH1") (pin "7") (pinfunction "7_7") (pintype "passive"))
      (node (ref "IH5") (pin "11") (pinfunction "11_11") (pintype "passive"))
      (node (ref "IH5") (pin "15") (pinfunction "15_15") (pintype "passive"))
      (node (ref "IH5") (pin "3") (pinfunction "3_3") (pintype "passive"))
      (node (ref "IH5") (pin "7") (pinfunction "7_7") (pintype "passive"))
      (node (ref "U4") (pin "7") (pinfunction "~{Y7}_7") (pintype "output"))
    )
    (net (code "37") (name "BC_3") (class "Default")
      (node (ref "IH2") (pin "1") (pinfunction "1_1") (pintype "passive"))
      (node (ref "IH2") (pin "13") (pinfunction "13_13") (pintype "passive"))
      (node (ref "IH2") (pin "5") (pinfunction "5_5") (pintype "passive"))
      (node (ref "IH2") (pin "9") (pinfunction "9_9") (pintype "passive"))
      (node (ref "IH6") (pin "1") (pinfunction "1_1") (pintype "passive"))
      (node (ref "IH6") (pin "13") (pinfunction "13_13") (pintype "passive"))
      (node (ref "IH6") (pin "5") (pinfunction "5_5") (pintype "passive"))
      (node (ref "IH6") (pin "9") (pinfunction "9_9") (pintype "passive"))
      (node (ref "U4") (pin "13") (pinfunction "~{Y2}_13") (pintype "output"))
    )
    (net (code "38") (name "BC_4") (class "Default")
      (node (ref "IH2") (pin "11") (pinfunction "11_11") (pintype "passive"))
      (node (ref "IH2") (pin "15") (pinfunction "15_15") (pintype "passive"))
      (node (ref "IH2") (pin "3") (pinfunction "3_3") (pintype "passive"))
      (node (ref "IH2") (pin "7") (pinfunction "7_7") (pintype "passive"))
      (node (ref "IH6") (pin "11") (pinfunction "11_11") (pintype "passive"))
      (node (ref "IH6") (pin "15") (pinfunction "15_15") (pintype "passive"))
      (node (ref "IH6") (pin "3") (pinfunction "3_3") (pintype "passive"))
      (node (ref "IH6") (pin "7") (pinfunction "7_7") (pintype "passive"))
      (node (ref "U4") (pin "14") (pinfunction "~{Y1}_14") (pintype "output"))
    )
    (net (code "39") (name "BC_5") (class "Default")
      (node (ref "IH3") (pin "1") (pinfunction "1_1") (pintype "passive"))
      (node (ref "IH3") (pin "13") (pinfunction "13_13") (pintype "passive"))
      (node (ref "IH3") (pin "5") (pinfunction "5_5") (pintype "passive"))
      (node (ref "IH3") (pin "9") (pinfunction "9_9") (pintype "passive"))
      (node (ref "IH7") (pin "1") (pinfunction "1_1") (pintype "passive"))
      (node (ref "IH7") (pin "13") (pinfunction "13_13") (pintype "passive"))
      (node (ref "IH7") (pin "5") (pinfunction "5_5") (pintype "passive"))
      (node (ref "IH7") (pin "9") (pinfunction "9_9") (pintype "passive"))
      (node (ref "U4") (pin "11") (pinfunction "~{Y4}_11") (pintype "output"))
    )
    (net (code "40") (name "BC_6") (class "Default")
      (node (ref "IH3") (pin "11") (pinfunction "11_11") (pintype "passive"))
      (node (ref "IH3") (pin "15") (pinfunction "15_15") (pintype "passive"))
      (node (ref "IH3") (pin "3") (pinfunction "3_3") (pintype "passive"))
      (node (ref "IH3") (pin "7") (pinfunction "7_7") (pintype "passive"))
      (node (ref "IH7") (pin "11") (pinfunction "11_11") (pintype "passive"))
      (node (ref "IH7") (pin "15") (pinfunction "15_15") (pintype "passive"))
      (node (ref "IH7") (pin "3") (pinfunction "3_3") (pintype "passive"))
      (node (ref "IH7") (pin "7") (pinfunction "7_7") (pintype "passive"))
      (node (ref "U4") (pin "12") (pinfunction "~{Y3}_12") (pintype "output"))
    )
    (net (code "41") (name "BC_7") (class "Default")
      (node (ref "IH4") (pin "1") (pinfunction "1_1") (pintype "passive"))
      (node (ref "IH4") (pin "13") (pinfunction "13_13") (pintype "passive"))
      (node (ref "IH4") (pin "5") (pinfunction "5_5") (pintype "passive"))
      (node (ref "IH4") (pin "9") (pinfunction "9_9") (pintype "passive"))
      (node (ref "IH8") (pin "1") (pinfunction "1_1") (pintype "passive"))
      (node (ref "IH8") (pin "13") (pinfunction "13_13") (pintype "passive"))
      (node (ref "IH8") (pin "5") (pinfunction "5_5") (pintype "passive"))
      (node (ref "IH8") (pin "9") (pinfunction "9_9") (pintype "passive"))
      (node (ref "U4") (pin "10") (pinfunction "~{Y5}_10") (pintype "output"))
    )
    (net (code "42") (name "BC_8") (class "Default")
      (node (ref "IH4") (pin "11") (pinfunction "11_11") (pintype "passive"))
      (node (ref "IH4") (pin "15") (pinfunction "15_15") (pintype "passive"))
      (node (ref "IH4") (pin "3") (pinfunction "3_3") (pintype "passive"))
      (node (ref "IH4") (pin "7") (pinfunction "7_7") (pintype "passive"))
      (node (ref "IH8") (pin "11") (pinfunction "11_11") (pintype "passive"))
      (node (ref "IH8") (pin "15") (pinfunction "15_15") (pintype "passive"))
      (node (ref "IH8") (pin "3") (pinfunction "3_3") (pintype "passive"))
      (node (ref "IH8") (pin "7") (pinfunction "7_7") (pintype "passive"))
      (node (ref "U4") (pin "9") (pinfunction "~{Y6}_9") (pintype "output"))
    )
    (net (code "43") (name "BOOT0") (class "Default")
      (node (ref "R3") (pin "2") (pinfunction "2_2") (pintype "passive"))
      (node (ref "U1") (pin "60") (pinfunction "BOOT0_60") (pintype "bidirectional"))
    )
    (net (code "44") (name "BR_1") (class "Default")
      (node (ref "D1") (pin "3") (pinfunction "3_3") (pintype "passive"))
      (node (ref "D2") (pin "3") (pinfunction "3_3") (pintype "passive"))
      (node (ref "D3") (pin "3") (pinfunction "3_3") (pintype "passive"))
      (node (ref "D4") (pin "3") (pinfunction "3_3") (pintype "passive"))
      (node (ref "R9") (pin "2") (pinfunction "2_2") (pintype "passive"))
      (node (ref "U1") (pin "20") (pinfunction "PA4_20") (pintype "bidirectional"))
    )
    (net (code "45") (name "BR_2") (class "Default")
      (node (ref "D5") (pin "3") (pinfunction "3_3") (pintype "passive"))
      (node (ref "D6") (pin "3") (pinfunction "3_3") (pintype "passive"))
      (node (ref "D7") (pin "3") (pinfunction "3_3") (pintype "passive"))
      (node (ref "D8") (pin "3") (pinfunction "3_3") (pintype "passive"))
      (node (ref "R11") (pin "2") (pinfunction "2_2") (pintype "passive"))
      (node (ref "U1") (pin "21") (pinfunction "PA5_21") (pintype "bidirectional"))
    )
    (net (code "46") (name "BR_3") (class "Default")
      (node (ref "D10") (pin "3") (pinfunction "3_3") (pintype "passive"))
      (node (ref "D11") (pin "3") (pinfunction "3_3") (pintype "passive"))
      (node (ref "D12") (pin "3") (pinfunction "3_3") (pintype "passive"))
      (node (ref "D9") (pin "3") (pinfunction "3_3") (pintype "passive"))
      (node (ref "R13") (pin "2") (pinfunction "2_2") (pintype "passive"))
      (node (ref "U1") (pin "24") (pinfunction "PC4_24") (pintype "bidirectional"))
    )
    (net (code "47") (name "BR_4") (class "Default")
      (node (ref "D13") (pin "3") (pinfunction "3_3") (pintype "passive"))
      (node (ref "D14") (pin "3") (pinfunction "3_3") (pintype "passive"))
      (node (ref "D15") (pin "3") (pinfunction "3_3") (pintype "passive"))
      (node (ref "D16") (pin "3") (pinfunction "3_3") (pintype "passive"))
      (node (ref "R14") (pin "2") (pinfunction "2_2") (pintype "passive"))
      (node (ref "U1") (pin "25") (pinfunction "PC5_25") (pintype "bidirectional"))
    )
    (net (code "48") (name "BR_5") (class "Default")
      (node (ref "D30") (pin "3") (pinfunction "3_3") (pintype "passive"))
      (node (ref "D31") (pin "3") (pinfunction "3_3") (pintype "passive"))
      (node (ref "D32") (pin "3") (pinfunction "3_3") (pintype "passive"))
      (node (ref "D33") (pin "3") (pinfunction "3_3") (pintype "passive"))
      (node (ref "R15") (pin "2") (pinfunction "2_2") (pintype "passive"))
      (node (ref "U1") (pin "30") (pinfunction "PB11_30") (pintype "bidirectional"))
    )
    (net (code "49") (name "BR_6") (class "Default")
      (node (ref "D26") (pin "3") (pinfunction "3_3") (pintype "passive"))
      (node (ref "D27") (pin "3") (pinfunction "3_3") (pintype "passive"))
      (node (ref "D28") (pin "3") (pinfunction "3_3") (pintype "passive"))
      (node (ref "D29") (pin "3") (pinfunction "3_3") (pintype "passive"))
      (node (ref "R16") (pin "2") (pinfunction "2_2") (pintype "passive"))
      (node (ref "U1") (pin "29") (pinfunction "PB10_29") (pintype "bidirectional"))
    )
    (net (code "50") (name "BR_7") (class "Default")
      (node (ref "D22") (pin "3") (pinfunction "3_3") (pintype "passive"))
      (node (ref "D23") (pin "3") (pinfunction "3_3") (pintype "passive"))
      (node (ref "D24") (pin "3") (pinfunction "3_3") (pintype "passive"))
      (node (ref "D25") (pin "3") (pinfunction "3_3") (pintype "passive"))
      (node (ref "R17") (pin "2") (pinfunction "2_2") (pintype "passive"))
      (node (ref "U1") (pin "28") (pinfunction "PB2_28") (pintype "bidirectional"))
    )
    (net (code "51") (name "BR_8") (class "Default")
      (node (ref "D18") (pin "3") (pinfunction "3_3") (pintype "passive"))
      (node (ref "D19") (pin "3") (pinfunction "3_3") (pintype "passive"))
      (node (ref "D20") (pin "3") (pinfunction "3_3") (pintype "passive"))
      (node (ref "D21") (pin "3") (pinfunction "3_3") (pintype "passive"))
      (node (ref "R18") (pin "2") (pinfunction "2_2") (pintype "passive"))
      (node (ref "U1") (pin "27") (pinfunction "PB1_27") (pintype "bidirectional"))
    )
    (net (code "52") (name "BTLDR_BUTTON") (class "Default")
      (node (ref "CONN2") (pin "1") (pinfunction "1_1") (pintype "passive"))
      (node (ref "U1") (pin "56") (pinfunction "PB4_56") (pintype "bidirectional"))
    )
    (net (code "53") (name "D+") (class "Default")
      (node (ref "R1") (pin "2") (pinfunction "2_2") (pintype "passive"))
      (node (ref "U1") (pin "45") (pinfunction "PA12_45") (pintype "bidirectional"))
    )
    (net (code "54") (name "D+X") (class "Default")
      (node (ref "CONN1") (pin "D+") (pinfunction "D+_D+") (pintype "bidirectional"))
      (node (ref "D17") (pin "3") (pinfunction "I/O2_3") (pintype "passive"))
      (node (ref "R1") (pin "1") (pinfunction "1_1") (pintype "passive"))
    )
    (net (code "55") (name "D-") (class "Default")
      (node (ref "R2") (pin "1") (pinfunction "1_1") (pintype "passive"))
      (node (ref "U1") (pin "44") (pinfunction "PA11_44") (pintype "bidirectional"))
    )
    (net (code "56") (name "D-X") (class "Default")
      (node (ref "CONN1") (pin "D-") (pinfunction "D-_D-") (pintype "bidirectional"))
      (node (ref "D17") (pin "2") (pinfunction "I/O1_2") (pintype "passive"))
      (node (ref "R2") (pin "2") (pinfunction "2_2") (pintype "passive"))
    )
    (net (code "57") (name "DEC_DI_A0") (class "Default")
      (node (ref "U1") (pin "39") (pinfunction "PC8_39") (pintype "bidirectional"))
      (node (ref "U4") (pin "1") (pinfunction "A0_1") (pintype "input"))
    )
    (net (code "58") (name "DEC_DI_A1") (class "Default")
      (node (ref "U1") (pin "40") (pinfunction "PC9_40") (pintype "bidirectional"))
      (node (ref "U4") (pin "2") (pinfunction "A1_2") (pintype "input"))
    )
    (net (code "59") (name "DEC_DI_A2") (class "Default")
      (node (ref "U1") (pin "41") (pinfunction "PA8_41") (pintype "bidirectional"))
      (node (ref "U4") (pin "3") (pinfunction "A2_3") (pintype "input"))
    )
    (net (code "60") (name "GND") (class "Default")
      (node (ref "AH1") (pin "1") (pinfunction "1_1") (pintype "passive"))
      (node (ref "AH1") (pin "10") (pinfunction "4_10") (pintype "passive"))
      (node (ref "AH1") (pin "13") (pinfunction "5_13") (pintype "passive"))
      (node (ref "AH1") (pin "16") (pinfunction "6_16") (pintype "passive"))
      (node (ref "AH1") (pin "19") (pinfunction "7_19") (pintype "passive"))
      (node (ref "AH1") (pin "22") (pinfunction "8_22") (pintype "passive"))
      (node (ref "AH1") (pin "4") (pinfunction "2_4") (pintype "passive"))
      (node (ref "AH1") (pin "7") (pinfunction "3_7") (pintype "passive"))
      (node (ref "AH2") (pin "1") (pinfunction "1_1") (pintype "passive"))
      (node (ref "AH2") (pin "10") (pinfunction "4_10") (pintype "passive"))
      (node (ref "AH2") (pin "13") (pinfunction "5_13") (pintype "passive"))
      (node (ref "AH2") (pin "16") (pinfunction "6_16") (pintype "passive"))
      (node (ref "AH2") (pin "19") (pinfunction "7_19") (pintype "passive"))
      (node (ref "AH2") (pin "22") (pinfunction "8_22") (pintype "passive"))
      (node (ref "AH2") (pin "4") (pinfunction "2_4") (pintype "passive"))
      (node (ref "AH2") (pin "7") (pinfunction "3_7") (pintype "passive"))
      (node (ref "AH3") (pin "1") (pinfunction "1_1") (pintype "passive"))
      (node (ref "AH3") (pin "10") (pinfunction "4_10") (pintype "passive"))
      (node (ref "AH3") (pin "13") (pinfunction "5_13") (pintype "passive"))
      (node (ref "AH3") (pin "16") (pinfunction "6_16") (pintype "passive"))
      (node (ref "AH3") (pin "19") (pinfunction "7_19") (pintype "passive"))
      (node (ref "AH3") (pin "22") (pinfunction "8_22") (pintype "passive"))
      (node (ref "AH3") (pin "4") (pinfunction "2_4") (pintype "passive"))
      (node (ref "AH3") (pin "7") (pinfunction "3_7") (pintype "passive"))
      (node (ref "AH4") (pin "1") (pinfunction "1_1") (pintype "passive"))
      (node (ref "AH4") (pin "10") (pinfunction "4_10") (pintype "passive"))
      (node (ref "AH4") (pin "13") (pinfunction "5_13") (pintype "passive"))
      (node (ref "AH4") (pin "16") (pinfunction "6_16") (pintype "passive"))
      (node (ref "AH4") (pin "19") (pinfunction "7_19") (pintype "passive"))
      (node (ref "AH4") (pin "22") (pinfunction "8_22") (pintype "passive"))
      (node (ref "AH4") (pin "4") (pinfunction "2_4") (pintype "passive"))
      (node (ref "AH4") (pin "7") (pinfunction "3_7") (pintype "passive"))
      (node (ref "C1") (pin "1") (pinfunction "1_1") (pintype "passive"))
      (node (ref "C10") (pin "2") (pinfunction "2_2") (pintype "passive"))
      (node (ref "C11") (pin "2") (pinfunction "2_2") (pintype "passive"))
      (node (ref "C15") (pin "1") (pinfunction "1_1") (pintype "passive"))
      (node (ref "C16") (pin "2") (pinfunction "2_2") (pintype "passive"))
      (node (ref "C17") (pin "2") (pinfunction "2_2") (pintype "passive"))
      (node (ref "C18") (pin "1") (pinfunction "1_1") (pintype "passive"))
      (node (ref "C19") (pin "1") (pinfunction "1_1") (pintype "passive"))
      (node (ref "C2") (pin "2") (pinfunction "2_2") (pintype "passive"))
      (node (ref "C20") (pin "1") (pinfunction "1_1") (pintype "passive"))
      (node (ref "C21") (pin "2") (pinfunction "2_2") (pintype "passive"))
      (node (ref "C22") (pin "2") (pinfunction "2_2") (pintype "passive"))
      (node (ref "C23") (pin "2") (pinfunction "2_2") (pintype "passive"))
      (node (ref "C24") (pin "2") (pinfunction "2_2") (pintype "passive"))
      (node (ref "C3") (pin "2") (pinfunction "2_2") (pintype "passive"))
      (node (ref "C4") (pin "1") (pinfunction "1_1") (pintype "passive"))
      (node (ref "C5") (pin "2") (pinfunction "2_2") (pintype "passive"))
      (node (ref "C6") (pin "1") (pinfunction "1_1") (pintype "passive"))
      (node (ref "C7") (pin "2") (pinfunction "2_2") (pintype "passive"))
      (node (ref "C8") (pin "2") (pinfunction "2_2") (pintype "passive"))
      (node (ref "C9") (pin "2") (pinfunction "2_2") (pintype "passive"))
      (node (ref "CONN1") (pin "GND") (pinfunction "GND_GND") (pintype "bidirectional"))
      (node (ref "CONN2") (pin "2") (pinfunction "2_2") (pintype "passive"))
      (node (ref "CONN4") (pin "2") (pinfunction "2_2") (pintype "passive"))
      (node (ref "CONN6") (pin "3") (pinfunction "3_3") (pintype "passive"))
      (node (ref "CONN7") (pin "3") (pinfunction "3_3") (pintype "passive"))
      (node (ref "CONN8") (pin "2") (pinfunction "2_2") (pintype "passive"))
      (node (ref "D17") (pin "1") (pinfunction "GND_1") (pintype "passive"))
      (node (ref "D35") (pin "C") (pinfunction "C_C") (pintype "passive"))
      (node (ref "D36") (pin "C") (pinfunction "C_C") (pintype "passive"))
      (node (ref "D37") (pin "C") (pinfunction "C_C") (pintype "passive"))
      (node (ref "L1") (pin "1") (pinfunction "1_1") (pintype "passive"))
      (node (ref "R3") (pin "1") (pinfunction "1_1") (pintype "passive"))
      (node (ref "U1") (pin "12") (pinfunction "VSSA_12") (pintype "bidirectional"))
      (node (ref "U1") (pin "18") (pinfunction "VSS_18") (pintype "bidirectional"))
      (node (ref "U1") (pin "63") (pinfunction "VSS_63") (pintype "bidirectional"))
      (node (ref "U2") (pin "5") (pinfunction "GND_5") (pintype "power_in"))
      (node (ref "U3") (pin "4") (pinfunction "GND_4") (pintype "power_in"))
      (node (ref "U3") (pin "9") (pinfunction "GND_9") (pintype "power_in"))
      (node (ref "U4") (pin "4") (pinfunction "~{E1}_4") (pintype "input"))
      (node (ref "U4") (pin "5") (pinfunction "~{E2}_5") (pintype "input"))
      (node (ref "U4") (pin "8") (pinfunction "GND_8") (pintype "power_in"))
      (node (ref "U5") (pin "12") (pinfunction "GND_12") (pintype "passive"))
      (node (ref "U5") (pin "15") (pinfunction "~{E}_15") (pintype "input"))
      (node (ref "U6") (pin "12") (pinfunction "GND_12") (pintype "passive"))
      (node (ref "U6") (pin "15") (pinfunction "~{E}_15") (pintype "input"))
      (node (ref "U7") (pin "1") (pinfunction "1~{(OE})_1") (pintype "bidirectional"))
      (node (ref "U7") (pin "10") (pinfunction "3~{(OE})_10") (pintype "bidirectional"))
      (node (ref "U7") (pin "4") (pinfunction "2~{(OE})_4") (pintype "bidirectional"))
      (node (ref "U7") (pin "7") (pinfunction "VEE_7") (pintype "passive"))
      (node (ref "VR2") (pin "2") (pinfunction "GND_2") (pintype "passive"))
      (node (ref "Y1") (pin "2") (pinfunction "VEE_2") (pintype "passive"))
      (node (ref "Y1") (pin "4") (pinfunction "VEE_4") (pintype "passive"))
    )
    (net (code "61") (name "LC_1") (class "Default")
      (node (ref "OH1") (pin "10") (pinfunction "10_10") (pintype "passive"))
      (node (ref "OH1") (pin "12") (pinfunction "12_12") (pintype "passive"))
      (node (ref "OH1") (pin "2") (pinfunction "2_2") (pintype "passive"))
      (node (ref "OH1") (pin "4") (pinfunction "4_4") (pintype "passive"))
      (node (ref "OH1") (pin "6") (pinfunction "6_6") (pintype "passive"))
      (node (ref "OH1") (pin "8") (pinfunction "8_8") (pintype "passive"))
      (node (ref "U3") (pin "2") (pinfunction "DIG_0_2") (pintype "output"))
    )
    (net (code "62") (name "LC_2") (class "Default")
      (node (ref "OH2") (pin "10") (pinfunction "10_10") (pintype "passive"))
      (node (ref "OH2") (pin "12") (pinfunction "12_12") (pintype "passive"))
      (node (ref "OH2") (pin "2") (pinfunction "2_2") (pintype "passive"))
      (node (ref "OH2") (pin "4") (pinfunction "4_4") (pintype "passive"))
      (node (ref "OH2") (pin "6") (pinfunction "6_6") (pintype "passive"))
      (node (ref "OH2") (pin "8") (pinfunction "8_8") (pintype "passive"))
      (node (ref "U3") (pin "3") (pinfunction "DIG_4_3") (pintype "output"))
    )
    (net (code "63") (name "LC_3") (class "Default")
      (node (ref "OH3") (pin "10") (pinfunction "10_10") (pintype "passive"))
      (node (ref "OH3") (pin "12") (pinfunction "12_12") (pintype "passive"))
      (node (ref "OH3") (pin "2") (pinfunction "2_2") (pintype "passive"))
      (node (ref "OH3") (pin "4") (pinfunction "4_4") (pintype "passive"))
      (node (ref "OH3") (pin "6") (pinfunction "6_6") (pintype "passive"))
      (node (ref "OH3") (pin "8") (pinfunction "8_8") (pintype "passive"))
      (node (ref "U3") (pin "5") (pinfunction "DIG_6_5") (pintype "output"))
    )
    (net (code "64") (name "LC_4") (class "Default")
      (node (ref "OH4") (pin "10") (pinfunction "10_10") (pintype "passive"))
      (node (ref "OH4") (pin "12") (pinfunction "12_12") (pintype "passive"))
      (node (ref "OH4") (pin "2") (pinfunction "2_2") (pintype "passive"))
      (node (ref "OH4") (pin "4") (pinfunction "4_4") (pintype "passive"))
      (node (ref "OH4") (pin "6") (pinfunction "6_6") (pintype "passive"))
      (node (ref "OH4") (pin "8") (pinfunction "8_8") (pintype "passive"))
      (node (ref "U3") (pin "6") (pinfunction "DIG_2_6") (pintype "output"))
    )
    (net (code "65") (name "LC_5") (class "Default")
      (node (ref "OH5") (pin "10") (pinfunction "10_10") (pintype "passive"))
      (node (ref "OH5") (pin "12") (pinfunction "12_12") (pintype "passive"))
      (node (ref "OH5") (pin "2") (pinfunction "2_2") (pintype "passive"))
      (node (ref "OH5") (pin "4") (pinfunction "4_4") (pintype "passive"))
      (node (ref "OH5") (pin "6") (pinfunction "6_6") (pintype "passive"))
      (node (ref "OH5") (pin "8") (pinfunction "8_8") (pintype "passive"))
      (node (ref "U3") (pin "7") (pinfunction "DIG_3_7") (pintype "output"))
    )
    (net (code "66") (name "LC_6") (class "Default")
      (node (ref "OH6") (pin "10") (pinfunction "10_10") (pintype "passive"))
      (node (ref "OH6") (pin "12") (pinfunction "12_12") (pintype "passive"))
      (node (ref "OH6") (pin "2") (pinfunction "2_2") (pintype "passive"))
      (node (ref "OH6") (pin "4") (pinfunction "4_4") (pintype "passive"))
      (node (ref "OH6") (pin "6") (pinfunction "6_6") (pintype "passive"))
      (node (ref "OH6") (pin "8") (pinfunction "8_8") (pintype "passive"))
      (node (ref "U3") (pin "8") (pinfunction "DIG_7_8") (pintype "output"))
    )
    (net (code "67") (name "LC_7") (class "Default")
      (node (ref "OH7") (pin "10") (pinfunction "10_10") (pintype "passive"))
      (node (ref "OH7") (pin "12") (pinfunction "12_12") (pintype "passive"))
      (node (ref "OH7") (pin "2") (pinfunction "2_2") (pintype "passive"))
      (node (ref "OH7") (pin "4") (pinfunction "4_4") (pintype "passive"))
      (node (ref "OH7") (pin "6") (pinfunction "6_6") (pintype "passive"))
      (node (ref "OH7") (pin "8") (pinfunction "8_8") (pintype "passive"))
      (node (ref "U3") (pin "10") (pinfunction "DIG_5_10") (pintype "output"))
    )
    (net (code "68") (name "LC_8") (class "Default")
      (node (ref "OH8") (pin "10") (pinfunction "10_10") (pintype "passive"))
      (node (ref "OH8") (pin "12") (pinfunction "12_12") (pintype "passive"))
      (node (ref "OH8") (pin "2") (pinfunction "2_2") (pintype "passive"))
      (node (ref "OH8") (pin "4") (pinfunction "4_4") (pintype "passive"))
      (node (ref "OH8") (pin "6") (pinfunction "6_6") (pintype "passive"))
      (node (ref "OH8") (pin "8") (pinfunction "8_8") (pintype "passive"))
      (node (ref "U3") (pin "11") (pinfunction "DIG_1_11") (pintype "output"))
    )
    (net (code "69") (name "LR_1_MI") (class "Default")
      (node (ref "U1") (pin "62") (pinfunction "PB9_62") (pintype "bidirectional"))
    )
    (net (code "70") (name "LR_1_MO") (class "Default")
      (node (ref "OH1") (pin "1") (pinfunction "1_1") (pintype "passive"))
      (node (ref "OH2") (pin "1") (pinfunction "1_1") (pintype "passive"))
      (node (ref "OH3") (pin "1") (pinfunction "1_1") (pintype "passive"))
      (node (ref "OH4") (pin "1") (pinfunction "1_1") (pintype "passive"))
      (node (ref "OH5") (pin "1") (pinfunction "1_1") (pintype "passive"))
      (node (ref "OH6") (pin "1") (pinfunction "1_1") (pintype "passive"))
      (node (ref "OH7") (pin "1") (pinfunction "1_1") (pintype "passive"))
      (node (ref "OH8") (pin "1") (pinfunction "1_1") (pintype "passive"))
      (node (ref "U3") (pin "23") (pinfunction "SEG_D_23") (pintype "output"))
    )
    (net (code "71") (name "LR_2_MI") (class "Default")
      (node (ref "U1") (pin "61") (pinfunction "PB8_61") (pintype "bidirectional"))
    )
    (net (code "72") (name "LR_2_MO") (class "Default")
      (node (ref "OH1") (pin "3") (pinfunction "3_3") (pintype "passive"))
      (node (ref "OH2") (pin "3") (pinfunction "3_3") (pintype "passive"))
      (node (ref "OH3") (pin "3") (pinfunction "3_3") (pintype "passive"))
      (node (ref "OH4") (pin "3") (pinfunction "3_3") (pintype "passive"))
      (node (ref "OH5") (pin "3") (pinfunction "3_3") (pintype "passive"))
      (node (ref "OH6") (pin "3") (pinfunction "3_3") (pintype "passive"))
      (node (ref "OH7") (pin "3") (pinfunction "3_3") (pintype "passive"))
      (node (ref "OH8") (pin "3") (pinfunction "3_3") (pintype "passive"))
      (node (ref "U3") (pin "22") (pinfunction "SEG_DP_22") (pintype "output"))
    )
    (net (code "73") (name "LR_3_MI") (class "Default")
      (node (ref "U1") (pin "17") (pinfunction "PA3_17") (pintype "bidirectional"))
    )
    (net (code "74") (name "LR_3_MO") (class "Default")
      (node (ref "OH1") (pin "9") (pinfunction "9_9") (pintype "passive"))
      (node (ref "OH2") (pin "9") (pinfunction "9_9") (pintype "passive"))
      (node (ref "OH3") (pin "9") (pinfunction "9_9") (pintype "passive"))
      (node (ref "OH4") (pin "9") (pinfunction "9_9") (pintype "passive"))
      (node (ref "OH5") (pin "9") (pinfunction "9_9") (pintype "passive"))
      (node (ref "OH6") (pin "9") (pinfunction "9_9") (pintype "passive"))
      (node (ref "OH7") (pin "9") (pinfunction "9_9") (pintype "passive"))
      (node (ref "OH8") (pin "9") (pinfunction "9_9") (pintype "passive"))
      (node (ref "U3") (pin "17") (pinfunction "SEG_G_17") (pintype "output"))
    )
    (net (code "75") (name "LR_4_MI") (class "Default")
      (node (ref "U1") (pin "22") (pinfunction "PA6_22") (pintype "bidirectional"))
    )
    (net (code "76") (name "LR_4_MO") (class "Default")
      (node (ref "OH1") (pin "11") (pinfunction "11_11") (pintype "passive"))
      (node (ref "OH2") (pin "11") (pinfunction "11_11") (pintype "passive"))
      (node (ref "OH3") (pin "11") (pinfunction "11_11") (pintype "passive"))
      (node (ref "OH4") (pin "11") (pinfunction "11_11") (pintype "passive"))
      (node (ref "OH5") (pin "11") (pinfunction "11_11") (pintype "passive"))
      (node (ref "OH6") (pin "11") (pinfunction "11_11") (pintype "passive"))
      (node (ref "OH7") (pin "11") (pinfunction "11_11") (pintype "passive"))
      (node (ref "OH8") (pin "11") (pinfunction "11_11") (pintype "passive"))
      (node (ref "U3") (pin "16") (pinfunction "SEG_B_16") (pintype "output"))
    )
    (net (code "77") (name "LR_5_MI") (class "Default")
      (node (ref "U1") (pin "23") (pinfunction "PA7_23") (pintype "bidirectional"))
    )
    (net (code "78") (name "LR_5_MO") (class "Default")
      (node (ref "OH1") (pin "5") (pinfunction "5_5") (pintype "passive"))
      (node (ref "OH2") (pin "5") (pinfunction "5_5") (pintype "passive"))
      (node (ref "OH3") (pin "5") (pinfunction "5_5") (pintype "passive"))
      (node (ref "OH4") (pin "5") (pinfunction "5_5") (pintype "passive"))
      (node (ref "OH5") (pin "5") (pinfunction "5_5") (pintype "passive"))
      (node (ref "OH6") (pin "5") (pinfunction "5_5") (pintype "passive"))
      (node (ref "OH7") (pin "5") (pinfunction "5_5") (pintype "passive"))
      (node (ref "OH8") (pin "5") (pinfunction "5_5") (pintype "passive"))
      (node (ref "U3") (pin "21") (pinfunction "SEG_E_21") (pintype "output"))
    )
    (net (code "79") (name "LR_6_MI") (class "Default")
      (node (ref "U1") (pin "26") (pinfunction "PB0_26") (pintype "bidirectional"))
    )
    (net (code "80") (name "LR_6_MO") (class "Default")
      (node (ref "OH1") (pin "7") (pinfunction "7_7") (pintype "passive"))
      (node (ref "OH2") (pin "7") (pinfunction "7_7") (pintype "passive"))
      (node (ref "OH3") (pin "7") (pinfunction "7_7") (pintype "passive"))
      (node (ref "OH4") (pin "7") (pinfunction "7_7") (pintype "passive"))
      (node (ref "OH5") (pin "7") (pinfunction "7_7") (pintype "passive"))
      (node (ref "OH6") (pin "7") (pinfunction "7_7") (pintype "passive"))
      (node (ref "OH7") (pin "7") (pinfunction "7_7") (pintype "passive"))
      (node (ref "OH8") (pin "7") (pinfunction "7_7") (pintype "passive"))
      (node (ref "U3") (pin "20") (pinfunction "SEG_C_20") (pintype "output"))
    )
    (net (code "81") (name "MAX7219_CLK") (class "Default")
      (node (ref "U1") (pin "14") (pinfunction "PA0_14") (pintype "bidirectional"))
      (node (ref "U7") (pin "9") (pinfunction "3A_9") (pintype "bidirectional"))
    )
    (net (code "82") (name "MAX7219_DIN") (class "Default")
      (node (ref "U1") (pin "16") (pinfunction "PA2_16") (pintype "bidirectional"))
      (node (ref "U7") (pin "2") (pinfunction "1A_2") (pintype "bidirectional"))
    )
    (net (code "83") (name "MAX7219_LOAD") (class "Default")
      (node (ref "U1") (pin "15") (pinfunction "PA1_15") (pintype "bidirectional"))
      (node (ref "U7") (pin "5") (pinfunction "2A_5") (pintype "bidirectional"))
    )
    (net (code "84") (name "MIDI_IN") (class "Default")
      (node (ref "R4") (pin "2") (pinfunction "2_2") (pintype "passive"))
      (node (ref "U1") (pin "38") (pinfunction "PC7_38") (pintype "bidirectional"))
      (node (ref "U2") (pin "6") (pinfunction "VO_6") (pintype "output"))
    )
    (net (code "85") (name "MIDI_IN_LED") (class "Default")
      (node (ref "R7") (pin "2") (pinfunction "2_2") (pintype "passive"))
      (node (ref "U1") (pin "43") (pinfunction "PA10_43") (pintype "bidirectional"))
    )
    (net (code "86") (name "MIDI_OUT") (class "Default")
      (node (ref "R12") (pin "2") (pinfunction "2_2") (pintype "passive"))
      (node (ref "U1") (pin "37") (pinfunction "PC6_37") (pintype "bidirectional"))
    )
    (net (code "87") (name "MIDI_OUT_LED") (class "Default")
      (node (ref "R6") (pin "2") (pinfunction "2_2") (pintype "passive"))
      (node (ref "U1") (pin "42") (pinfunction "PA9_42") (pintype "bidirectional"))
    )
    (net (code "88") (name "MUX_COMMON_1") (class "Default")
      (node (ref "U1") (pin "10") (pinfunction "PC2_10") (pintype "bidirectional"))
      (node (ref "U5") (pin "1") (pinfunction "Z_1") (pintype "bidirectional"))
    )
    (net (code "89") (name "MUX_COMMON_2") (class "Default")
      (node (ref "U1") (pin "9") (pinfunction "PC1_9") (pintype "bidirectional"))
      (node (ref "U6") (pin "1") (pinfunction "Z_1") (pintype "bidirectional"))
    )
    (net (code "90") (name "MUX_S0") (class "Default")
      (node (ref "U1") (pin "35") (pinfunction "PB14_35") (pintype "bidirectional"))
      (node (ref "U5") (pin "10") (pinfunction "S0_10") (pintype "input"))
      (node (ref "U6") (pin "10") (pinfunction "S0_10") (pintype "input"))
    )
    (net (code "91") (name "MUX_S1") (class "Default")
      (node (ref "U1") (pin "36") (pinfunction "PB15_36") (pintype "bidirectional"))
      (node (ref "U5") (pin "11") (pinfunction "S1_11") (pintype "input"))
      (node (ref "U6") (pin "11") (pinfunction "S1_11") (pintype "input"))
    )
    (net (code "92") (name "MUX_S2") (class "Default")
      (node (ref "U1") (pin "33") (pinfunction "PB12_33") (pintype "bidirectional"))
      (node (ref "U5") (pin "14") (pinfunction "S2_14") (pintype "input"))
      (node (ref "U6") (pin "14") (pinfunction "S2_14") (pintype "input"))
    )
    (net (code "93") (name "MUX_S3") (class "Default")
      (node (ref "U1") (pin "34") (pinfunction "PB13_34") (pintype "bidirectional"))
      (node (ref "U5") (pin "13") (pinfunction "S3_13") (pintype "input"))
      (node (ref "U6") (pin "13") (pinfunction "S3_13") (pintype "input"))
    )
    (net (code "94") (name "NRST") (class "Default")
      (node (ref "C17") (pin "1") (pinfunction "1_1") (pintype "passive"))
      (node (ref "U1") (pin "7") (pinfunction "NRST_7") (pintype "bidirectional"))
    )
    (net (code "95") (name "Net-(C1-Pad2)") (class "Default")
      (node (ref "C1") (pin "2") (pinfunction "2_2") (pintype "passive"))
      (node (ref "U1") (pin "31") (pinfunction "VCAP_31") (pintype "bidirectional"))
    )
    (net (code "96") (name "Net-(C2-Pad1)") (class "Default")
      (node (ref "C2") (pin "1") (pinfunction "1_1") (pintype "passive"))
      (node (ref "U1") (pin "47") (pinfunction "VCAP_47") (pintype "bidirectional"))
    )
    (net (code "97") (name "Net-(CONN3-Pad4)") (class "Default")
      (node (ref "CONN3") (pin "4") (pinfunction "4_4") (pintype "bidirectional"))
      (node (ref "R5") (pin "1") (pinfunction "1_1") (pintype "passive"))
    )
    (net (code "98") (name "Net-(CONN4-Pad4)") (class "Default")
      (node (ref "CONN4") (pin "4") (pinfunction "4_4") (pintype "bidirectional"))
      (node (ref "R10") (pin "1") (pinfunction "1_1") (pintype "passive"))
    )
    (net (code "99") (name "Net-(CONN4-Pad5)") (class "Default")
      (node (ref "CONN4") (pin "5") (pinfunction "5_5") (pintype "bidirectional"))
      (node (ref "R12") (pin "1") (pinfunction "1_1") (pintype "passive"))
    )
    (net (code "100") (name "Net-(D1-Pad1)") (class "Default")
      (node (ref "D1") (pin "1") (pinfunction "1_1") (pintype "passive"))
      (node (ref "IH1") (pin "2") (pinfunction "2_2") (pintype "passive"))
    )
    (net (code "101") (name "Net-(D1-Pad2)") (class "Default")
      (node (ref "D1") (pin "2") (pinfunction "2_2") (pintype "passive"))
      (node (ref "IH1") (pin "8") (pinfunction "8_8") (pintype "passive"))
    )
    (net (code "102") (name "Net-(D2-Pad1)") (class "Default")
      (node (ref "D2") (pin "1") (pinfunction "1_1") (pintype "passive"))
      (node (ref "IH2") (pin "2") (pinfunction "2_2") (pintype "passive"))
    )
    (net (code "103") (name "Net-(D2-Pad2)") (class "Default")
      (node (ref "D2") (pin "2") (pinfunction "2_2") (pintype "passive"))
      (node (ref "IH2") (pin "8") (pinfunction "8_8") (pintype "passive"))
    )
    (net (code "104") (name "Net-(D3-Pad1)") (class "Default")
      (node (ref "D3") (pin "1") (pinfunction "1_1") (pintype "passive"))
      (node (ref "IH3") (pin "2") (pinfunction "2_2") (pintype "passive"))
    )
    (net (code "105") (name "Net-(D3-Pad2)") (class "Default")
      (node (ref "D3") (pin "2") (pinfunction "2_2") (pintype "passive"))
      (node (ref "IH3") (pin "8") (pinfunction "8_8") (pintype "passive"))
    )
    (net (code "106") (name "Net-(D4-Pad1)") (class "Default")
      (node (ref "D4") (pin "1") (pinfunction "1_1") (pintype "passive"))
      (node (ref "IH4") (pin "2") (pinfunction "2_2") (pintype "passive"))
    )
    (net (code "107") (name "Net-(D4-Pad2)") (class "Default")
      (node (ref "D4") (pin "2") (pinfunction "2_2") (pintype "passive"))
      (node (ref "IH4") (pin "8") (pinfunction "8_8") (pintype "passive"))
    )
    (net (code "108") (name "Net-(D5-Pad1)") (class "Default")
      (node (ref "D5") (pin "1") (pinfunction "1_1") (pintype "passive"))
      (node (ref "IH1") (pin "4") (pinfunction "4_4") (pintype "passive"))
    )
    (net (code "109") (name "Net-(D5-Pad2)") (class "Default")
      (node (ref "D5") (pin "2") (pinfunction "2_2") (pintype "passive"))
      (node (ref "IH1") (pin "6") (pinfunction "6_6") (pintype "passive"))
    )
    (net (code "110") (name "Net-(D6-Pad1)") (class "Default")
      (node (ref "D6") (pin "1") (pinfunction "1_1") (pintype "passive"))
      (node (ref "IH2") (pin "4") (pinfunction "4_4") (pintype "passive"))
    )
    (net (code "111") (name "Net-(D6-Pad2)") (class "Default")
      (node (ref "D6") (pin "2") (pinfunction "2_2") (pintype "passive"))
      (node (ref "IH2") (pin "6") (pinfunction "6_6") (pintype "passive"))
    )
    (net (code "112") (name "Net-(D7-Pad1)") (class "Default")
      (node (ref "D7") (pin "1") (pinfunction "1_1") (pintype "passive"))
      (node (ref "IH3") (pin "4") (pinfunction "4_4") (pintype "passive"))
    )
    (net (code "113") (name "Net-(D7-Pad2)") (class "Default")
      (node (ref "D7") (pin "2") (pinfunction "2_2") (pintype "passive"))
      (node (ref "IH3") (pin "6") (pinfunction "6_6") (pintype "passive"))
    )
    (net (code "114") (name "Net-(D8-Pad1)") (class "Default")
      (node (ref "D8") (pin "1") (pinfunction "1_1") (pintype "passive"))
      (node (ref "IH4") (pin "4") (pinfunction "4_4") (pintype "passive"))
    )
    (net (code "115") (name "Net-(D8-Pad2)") (class "Default")
      (node (ref "D8") (pin "2") (pinfunction "2_2") (pintype "passive"))
      (node (ref "IH4") (pin "6") (pinfunction "6_6") (pintype "passive"))
    )
    (net (code "116") (name "Net-(D9-Pad1)") (class "Default")
      (node (ref "D9") (pin "1") (pinfunction "1_1") (pintype "passive"))
      (node (ref "IH1") (pin "10") (pinfunction "10_10") (pintype "passive"))
    )
    (net (code "117") (name "Net-(D9-Pad2)") (class "Default")
      (node (ref "D9") (pin "2") (pinfunction "2_2") (pintype "passive"))
      (node (ref "IH1") (pin "16") (pinfunction "16_16") (pintype "passive"))
    )
    (net (code "118") (name "Net-(D10-Pad1)") (class "Default")
      (node (ref "D10") (pin "1") (pinfunction "1_1") (pintype "passive"))
      (node (ref "IH2") (pin "10") (pinfunction "10_10") (pintype "passive"))
    )
    (net (code "119") (name "Net-(D10-Pad2)") (class "Default")
      (node (ref "D10") (pin "2") (pinfunction "2_2") (pintype "passive"))
      (node (ref "IH2") (pin "16") (pinfunction "16_16") (pintype "passive"))
    )
    (net (code "120") (name "Net-(D11-Pad1)") (class "Default")
      (node (ref "D11") (pin "1") (pinfunction "1_1") (pintype "passive"))
      (node (ref "IH3") (pin "10") (pinfunction "10_10") (pintype "passive"))
    )
    (net (code "121") (name "Net-(D11-Pad2)") (class "Default")
      (node (ref "D11") (pin "2") (pinfunction "2_2") (pintype "passive"))
      (node (ref "IH3") (pin "16") (pinfunction "16_16") (pintype "passive"))
    )
    (net (code "122") (name "Net-(D12-Pad1)") (class "Default")
      (node (ref "D12") (pin "1") (pinfunction "1_1") (pintype "passive"))
      (node (ref "IH4") (pin "10") (pinfunction "10_10") (pintype "passive"))
    )
    (net (code "123") (name "Net-(D12-Pad2)") (class "Default")
      (node (ref "D12") (pin "2") (pinfunction "2_2") (pintype "passive"))
      (node (ref "IH4") (pin "16") (pinfunction "16_16") (pintype "passive"))
    )
    (net (code "124") (name "Net-(D13-Pad1)") (class "Default")
      (node (ref "D13") (pin "1") (pinfunction "1_1") (pintype "passive"))
      (node (ref "IH1") (pin "12") (pinfunction "12_12") (pintype "passive"))
    )
    (net (code "125") (name "Net-(D13-Pad2)") (class "Default")
      (node (ref "D13") (pin "2") (pinfunction "2_2") (pintype "passive"))
      (node (ref "IH1") (pin "14") (pinfunction "14_14") (pintype "passive"))
    )
    (net (code "126") (name "Net-(D14-Pad1)") (class "Default")
      (node (ref "D14") (pin "1") (pinfunction "1_1") (pintype "passive"))
      (node (ref "IH2") (pin "12") (pinfunction "12_12") (pintype "passive"))
    )
    (net (code "127") (name "Net-(D14-Pad2)") (class "Default")
      (node (ref "D14") (pin "2") (pinfunction "2_2") (pintype "passive"))
      (node (ref "IH2") (pin "14") (pinfunction "14_14") (pintype "passive"))
    )
    (net (code "128") (name "Net-(D15-Pad1)") (class "Default")
      (node (ref "D15") (pin "1") (pinfunction "1_1") (pintype "passive"))
      (node (ref "IH3") (pin "12") (pinfunction "12_12") (pintype "passive"))
    )
    (net (code "129") (name "Net-(D15-Pad2)") (class "Default")
      (node (ref "D15") (pin "2") (pinfunction "2_2") (pintype "passive"))
      (node (ref "IH3") (pin "14") (pinfunction "14_14") (pintype "passive"))
    )
    (net (code "130") (name "Net-(D16-Pad1)") (class "Default")
      (node (ref "D16") (pin "1") (pinfunction "1_1") (pintype "passive"))
      (node (ref "IH4") (pin "12") (pinfunction "12_12") (pintype "passive"))
    )
    (net (code "131") (name "Net-(D16-Pad2)") (class "Default")
      (node (ref "D16") (pin "2") (pinfunction "2_2") (pintype "passive"))
      (node (ref "IH4") (pin "14") (pinfunction "14_14") (pintype "passive"))
    )
    (net (code "132") (name "Net-(D18-Pad1)") (class "Default")
      (node (ref "D18") (pin "1") (pinfunction "1_1") (pintype "passive"))
      (node (ref "IH5") (pin "2") (pinfunction "2_2") (pintype "passive"))
    )
    (net (code "133") (name "Net-(D18-Pad2)") (class "Default")
      (node (ref "D18") (pin "2") (pinfunction "2_2") (pintype "passive"))
      (node (ref "IH5") (pin "8") (pinfunction "8_8") (pintype "passive"))
    )
    (net (code "134") (name "Net-(D19-Pad1)") (class "Default")
      (node (ref "D19") (pin "1") (pinfunction "1_1") (pintype "passive"))
      (node (ref "IH6") (pin "2") (pinfunction "2_2") (pintype "passive"))
    )
    (net (code "135") (name "Net-(D19-Pad2)") (class "Default")
      (node (ref "D19") (pin "2") (pinfunction "2_2") (pintype "passive"))
      (node (ref "IH6") (pin "8") (pinfunction "8_8") (pintype "passive"))
    )
    (net (code "136") (name "Net-(D20-Pad1)") (class "Default")
      (node (ref "D20") (pin "1") (pinfunction "1_1") (pintype "passive"))
      (node (ref "IH7") (pin "2") (pinfunction "2_2") (pintype "passive"))
    )
    (net (code "137") (name "Net-(D20-Pad2)") (class "Default")
      (node (ref "D20") (pin "2") (pinfunction "2_2") (pintype "passive"))
      (node (ref "IH7") (pin "8") (pinfunction "8_8") (pintype "passive"))
    )
    (net (code "138") (name "Net-(D21-Pad1)") (class "Default")
      (node (ref "D21") (pin "1") (pinfunction "1_1") (pintype "passive"))
      (node (ref "IH8") (pin "2") (pinfunction "2_2") (pintype "passive"))
    )
    (net (code "139") (name "Net-(D21-Pad2)") (class "Default")
      (node (ref "D21") (pin "2") (pinfunction "2_2") (pintype "passive"))
      (node (ref "IH8") (pin "8") (pinfunction "8_8") (pintype "passive"))
    )
    (net (code "140") (name "Net-(D22-Pad1)") (class "Default")
      (node (ref "D22") (pin "1") (pinfunction "1_1") (pintype "passive"))
      (node (ref "IH5") (pin "4") (pinfunction "4_4") (pintype "passive"))
    )
    (net (code "141") (name "Net-(D22-Pad2)") (class "Default")
      (node (ref "D22") (pin "2") (pinfunction "2_2") (pintype "passive"))
      (node (ref "IH5") (pin "6") (pinfunction "6_6") (pintype "passive"))
    )
    (net (code "142") (name "Net-(D23-Pad1)") (class "Default")
      (node (ref "D23") (pin "1") (pinfunction "1_1") (pintype "passive"))
      (node (ref "IH6") (pin "4") (pinfunction "4_4") (pintype "passive"))
    )
    (net (code "143") (name "Net-(D23-Pad2)") (class "Default")
      (node (ref "D23") (pin "2") (pinfunction "2_2") (pintype "passive"))
      (node (ref "IH6") (pin "6") (pinfunction "6_6") (pintype "passive"))
    )
    (net (code "144") (name "Net-(D24-Pad1)") (class "Default")
      (node (ref "D24") (pin "1") (pinfunction "1_1") (pintype "passive"))
      (node (ref "IH7") (pin "4") (pinfunction "4_4") (pintype "passive"))
    )
    (net (code "145") (name "Net-(D24-Pad2)") (class "Default")
      (node (ref "D24") (pin "2") (pinfunction "2_2") (pintype "passive"))
      (node (ref "IH7") (pin "6") (pinfunction "6_6") (pintype "passive"))
    )
    (net (code "146") (name "Net-(D25-Pad1)") (class "Default")
      (node (ref "D25") (pin "1") (pinfunction "1_1") (pintype "passive"))
      (node (ref "IH8") (pin "4") (pinfunction "4_4") (pintype "passive"))
    )
    (net (code "147") (name "Net-(D25-Pad2)") (class "Default")
      (node (ref "D25") (pin "2") (pinfunction "2_2") (pintype "passive"))
      (node (ref "IH8") (pin "6") (pinfunction "6_6") (pintype "passive"))
    )
    (net (code "148") (name "Net-(D26-Pad1)") (class "Default")
      (node (ref "D26") (pin "1") (pinfunction "1_1") (pintype "passive"))
      (node (ref "IH5") (pin "10") (pinfunction "10_10") (pintype "passive"))
    )
    (net (code "149") (name "Net-(D26-Pad2)") (class "Default")
      (node (ref "D26") (pin "2") (pinfunction "2_2") (pintype "passive"))
      (node (ref "IH5") (pin "16") (pinfunction "16_16") (pintype "passive"))
    )
    (net (code "150") (name "Net-(D27-Pad1)") (class "Default")
      (node (ref "D27") (pin "1") (pinfunction "1_1") (pintype "passive"))
      (node (ref "IH6") (pin "10") (pinfunction "10_10") (pintype "passive"))
    )
    (net (code "151") (name "Net-(D27-Pad2)") (class "Default")
      (node (ref "D27") (pin "2") (pinfunction "2_2") (pintype "passive"))
      (node (ref "IH6") (pin "16") (pinfunction "16_16") (pintype "passive"))
    )
    (net (code "152") (name "Net-(D28-Pad1)") (class "Default")
      (node (ref "D28") (pin "1") (pinfunction "1_1") (pintype "passive"))
      (node (ref "IH7") (pin "10") (pinfunction "10_10") (pintype "passive"))
    )
    (net (code "153") (name "Net-(D28-Pad2)") (class "Default")
      (node (ref "D28") (pin "2") (pinfunction "2_2") (pintype "passive"))
      (node (ref "IH7") (pin "16") (pinfunction "16_16") (pintype "passive"))
    )
    (net (code "154") (name "Net-(D29-Pad1)") (class "Default")
      (node (ref "D29") (pin "1") (pinfunction "1_1") (pintype "passive"))
      (node (ref "IH8") (pin "10") (pinfunction "10_10") (pintype "passive"))
    )
    (net (code "155") (name "Net-(D29-Pad2)") (class "Default")
      (node (ref "D29") (pin "2") (pinfunction "2_2") (pintype "passive"))
      (node (ref "IH8") (pin "16") (pinfunction "16_16") (pintype "passive"))
    )
    (net (code "156") (name "Net-(D30-Pad1)") (class "Default")
      (node (ref "D30") (pin "1") (pinfunction "1_1") (pintype "passive"))
      (node (ref "IH5") (pin "12") (pinfunction "12_12") (pintype "passive"))
    )
    (net (code "157") (name "Net-(D30-Pad2)") (class "Default")
      (node (ref "D30") (pin "2") (pinfunction "2_2") (pintype "passive"))
      (node (ref "IH5") (pin "14") (pinfunction "14_14") (pintype "passive"))
    )
    (net (code "158") (name "Net-(D31-Pad1)") (class "Default")
      (node (ref "D31") (pin "1") (pinfunction "1_1") (pintype "passive"))
      (node (ref "IH6") (pin "12") (pinfunction "12_12") (pintype "passive"))
    )
    (net (code "159") (name "Net-(D31-Pad2)") (class "Default")
      (node (ref "D31") (pin "2") (pinfunction "2_2") (pintype "passive"))
      (node (ref "IH6") (pin "14") (pinfunction "14_14") (pintype "passive"))
    )
    (net (code "160") (name "Net-(D32-Pad1)") (class "Default")
      (node (ref "D32") (pin "1") (pinfunction "1_1") (pintype "passive"))
      (node (ref "IH7") (pin "12") (pinfunction "12_12") (pintype "passive"))
    )
    (net (code "161") (name "Net-(D32-Pad2)") (class "Default")
      (node (ref "D32") (pin "2") (pinfunction "2_2") (pintype "passive"))
      (node (ref "IH7") (pin "14") (pinfunction "14_14") (pintype "passive"))
    )
    (net (code "162") (name "Net-(D33-Pad1)") (class "Default")
      (node (ref "D33") (pin "1") (pinfunction "1_1") (pintype "passive"))
      (node (ref "IH8") (pin "12") (pinfunction "12_12") (pintype "passive"))
    )
    (net (code "163") (name "Net-(D33-Pad2)") (class "Default")
      (node (ref "D33") (pin "2") (pinfunction "2_2") (pintype "passive"))
      (node (ref "IH8") (pin "14") (pinfunction "14_14") (pintype "passive"))
    )
    (net (code "164") (name "Net-(D35-PadA)") (class "Default")
      (node (ref "D35") (pin "A") (pinfunction "A_A") (pintype "passive"))
      (node (ref "R6") (pin "1") (pinfunction "1_1") (pintype "passive"))
    )
    (net (code "165") (name "Net-(D36-PadA)") (class "Default")
      (node (ref "D36") (pin "A") (pinfunction "A_A") (pintype "passive"))
      (node (ref "R7") (pin "1") (pinfunction "1_1") (pintype "passive"))
    )
    (net (code "166") (name "Net-(D37-PadA)") (class "Default")
      (node (ref "D37") (pin "A") (pinfunction "A_A") (pintype "passive"))
      (node (ref "R8") (pin "2") (pinfunction "2_2") (pintype "passive"))
    )
    (net (code "167") (name "Net-(U2-A)") (class "Default")
      (node (ref "D34") (pin "2") (pinfunction "2_2") (pintype "passive"))
      (node (ref "R5") (pin "2") (pinfunction "2_2") (pintype "passive"))
      (node (ref "U2") (pin "2") (pinfunction "A_2") (pintype "passive"))
    )
    (net (code "168") (name "Net-(U2-C)") (class "Default")
      (node (ref "CONN3") (pin "5") (pinfunction "5_5") (pintype "bidirectional"))
      (node (ref "D34") (pin "3") (pinfunction "3_3") (pintype "passive"))
      (node (ref "U2") (pin "3") (pinfunction "C_3") (pintype "passive"))
    )
    (net (code "169") (name "Net-(U3-CLK)") (class "Default")
      (node (ref "U3") (pin "13") (pinfunction "CLK_13") (pintype "input"))
      (node (ref "U7") (pin "8") (pinfunction "3Y_8") (pintype "bidirectional"))
    )
    (net (code "170") (name "Net-(U3-DIN)") (class "Default")
      (node (ref "U3") (pin "1") (pinfunction "DIN_1") (pintype "input"))
      (node (ref "U7") (pin "3") (pinfunction "1Y_3") (pintype "bidirectional"))
    )
    (net (code "171") (name "Net-(U3-ISET)") (class "Default")
      (node (ref "R19") (pin "1") (pinfunction "1_1") (pintype "passive"))
      (node (ref "U3") (pin "18") (pinfunction "ISET_18") (pintype "input"))
    )
    (net (code "172") (name "Net-(U3-LOAD)") (class "Default")
      (node (ref "U3") (pin "12") (pinfunction "LOAD_12") (pintype "input"))
      (node (ref "U7") (pin "6") (pinfunction "2Y_6") (pintype "bidirectional"))
    )
    (net (code "173") (name "OSC_IN") (class "Default")
      (node (ref "C23") (pin "1") (pinfunction "1_1") (pintype "passive"))
      (node (ref "U1") (pin "5") (pinfunction "PH0_5") (pintype "bidirectional"))
      (node (ref "Y1") (pin "1") (pinfunction "1_1") (pintype "passive"))
    )
    (net (code "174") (name "OSC_OUT") (class "Default")
      (node (ref "C24") (pin "1") (pinfunction "1_1") (pintype "passive"))
      (node (ref "U1") (pin "6") (pinfunction "PH1_6") (pintype "bidirectional"))
      (node (ref "Y1") (pin "3") (pinfunction "2_3") (pintype "passive"))
    )
    (net (code "175") (name "SCL") (class "Default")
      (node (ref "CONN6") (pin "2") (pinfunction "2_2") (pintype "passive"))
      (node (ref "U1") (pin "58") (pinfunction "PB6_58") (pintype "bidirectional"))
    )
    (net (code "176") (name "SDA") (class "Default")
      (node (ref "CONN6") (pin "1") (pinfunction "1_1") (pintype "passive"))
      (node (ref "U1") (pin "59") (pinfunction "PB7_59") (pintype "bidirectional"))
    )
    (net (code "177") (name "SWDCLK") (class "Default")
      (node (ref "CONN8") (pin "3") (pinfunction "3_3") (pintype "passive"))
      (node (ref "U1") (pin "49") (pinfunction "PA14_49") (pintype "bidirectional"))
    )
    (net (code "178") (name "SWDIO") (class "Default")
      (node (ref "CONN8") (pin "1") (pinfunction "1_1") (pintype "passive"))
      (node (ref "U1") (pin "46") (pinfunction "PA13_46") (pintype "bidirectional"))
    )
    (net (code "179") (name "UART_RX") (class "Default")
      (node (ref "CONN7") (pin "1") (pinfunction "1_1") (pintype "passive"))
      (node (ref "U1") (pin "54") (pinfunction "PD2_54") (pintype "bidirectional"))
    )
    (net (code "180") (name "UART_TX") (class "Default")
      (node (ref "CONN7") (pin "2") (pinfunction "2_2") (pintype "passive"))
      (node (ref "U1") (pin "53") (pinfunction "PC12_53") (pintype "bidirectional"))
    )
    (net (code "181") (name "USB_SHIELD") (class "Default")
      (node (ref "CONN1") (pin "S1") (pinfunction "S_S1") (pintype "passive"))
      (node (ref "CONN1") (pin "S2") (pinfunction "S_S2") (pintype "passive"))
      (node (ref "L1") (pin "2") (pinfunction "2_2") (pintype "passive"))
    )
    (net (code "182") (name "unconnected-(CONN3-Pad1)") (class "Default")
      (node (ref "CONN3") (pin "1") (pinfunction "1_1") (pintype "bidirectional"))
    )
    (net (code "183") (name "unconnected-(CONN3-Pad2)") (class "Default")
      (node (ref "CONN3") (pin "2") (pinfunction "2_2") (pintype "passive"))
    )
    (net (code "184") (name "unconnected-(CONN3-Pad3)") (class "Default")
      (node (ref "CONN3") (pin "3") (pinfunction "3_3") (pintype "bidirectional"))
    )
    (net (code "185") (name "unconnected-(CONN4-Pad1)") (class "Default")
      (node (ref "CONN4") (pin "1") (pinfunction "1_1") (pintype "bidirectional"))
    )
    (net (code "186") (name "unconnected-(CONN4-Pad3)") (class "Default")
      (node (ref "CONN4") (pin "3") (pinfunction "3_3") (pintype "bidirectional"))
    )
    (net (code "187") (name "unconnected-(D34-Pad1)") (class "Default")
      (node (ref "D34") (pin "1") (pinfunction "1_1") (pintype "passive"))
    )
    (net (code "188") (name "unconnected-(U1-PA15-Pad50)") (class "Default")
      (node (ref "U1") (pin "50") (pinfunction "PA15_50") (pintype "bidirectional"))
    )
    (net (code "189") (name "unconnected-(U1-PB3-Pad55)") (class "Default")
      (node (ref "U1") (pin "55") (pinfunction "PB3_55") (pintype "bidirectional"))
    )
    (net (code "190") (name "unconnected-(U1-PB5-Pad57)") (class "Default")
      (node (ref "U1") (pin "57") (pinfunction "PB5_57") (pintype "bidirectional"))
    )
    (net (code "191") (name "unconnected-(U1-PC0-Pad8)") (class "Default")
      (node (ref "U1") (pin "8") (pinfunction "PC0_8") (pintype "bidirectional"))
    )
    (net (code "192") (name "unconnected-(U1-PC3-Pad11)") (class "Default")
      (node (ref "U1") (pin "11") (pinfunction "PC3_11") (pintype "bidirectional"))
    )
    (net (code "193") (name "unconnected-(U1-PC10-Pad51)") (class "Default")
      (node (ref "U1") (pin "51") (pinfunction "PC10_51") (pintype "bidirectional"))
    )
    (net (code "194") (name "unconnected-(U1-PC11-Pad52)") (class "Default")
      (node (ref "U1") (pin "52") (pinfunction "PC11_52") (pintype "bidirectional"))
    )
    (net (code "195") (name "unconnected-(U1-PC13-Pad2)") (class "Default")
      (node (ref "U1") (pin "2") (pinfunction "PC13_2") (pintype "bidirectional"))
    )
    (net (code "196") (name "unconnected-(U1-PC14-Pad3)") (class "Default")
      (node (ref "U1") (pin "3") (pinfunction "PC14_3") (pintype "bidirectional"))
    )
    (net (code "197") (name "unconnected-(U1-PC15-Pad4)") (class "Default")
      (node (ref "U1") (pin "4") (pinfunction "PC15_4") (pintype "bidirectional"))
    )
    (net (code "198") (name "unconnected-(U3-DOUT-Pad24)") (class "Default")
      (node (ref "U3") (pin "24") (pinfunction "DOUT_24") (pintype "output"))
    )
    (net (code "199") (name "unconnected-(U3-SEG_A-Pad14)") (class "Default")
      (node (ref "U3") (pin "14") (pinfunction "SEG_A_14") (pintype "output"))
    )
    (net (code "200") (name "unconnected-(U3-SEG_F-Pad15)") (class "Default")
      (node (ref "U3") (pin "15") (pinfunction "SEG_F_15") (pintype "output"))
    )
    (net (code "201") (name "unconnected-(U7A-4A-Pad12)") (class "Default")
      (node (ref "U7") (pin "12") (pinfunction "4A_12") (pintype "bidirectional"))
    )
    (net (code "202") (name "unconnected-(U7A-4Y-Pad11)") (class "Default")
      (node (ref "U7") (pin "11") (pinfunction "4Y_11") (pintype "bidirectional"))
    )
    (net (code "203") (name "unconnected-(U7A-4~{(OE})-Pad13)") (class "Default")
      (node (ref "U7") (pin "13") (pinfunction "4~{(OE})_13") (pintype "bidirectional"))
    )
    (net (code "204") (name "unconnected-(VR2-ADJ-Pad4)") (class "Default")
      (node (ref "VR2") (pin "4") (pinfunction "ADJ_4") (pintype "passive"))
    )
  )
)
